# fig4-9.net
KiCad netlist of a schematic drawn in EAGLE
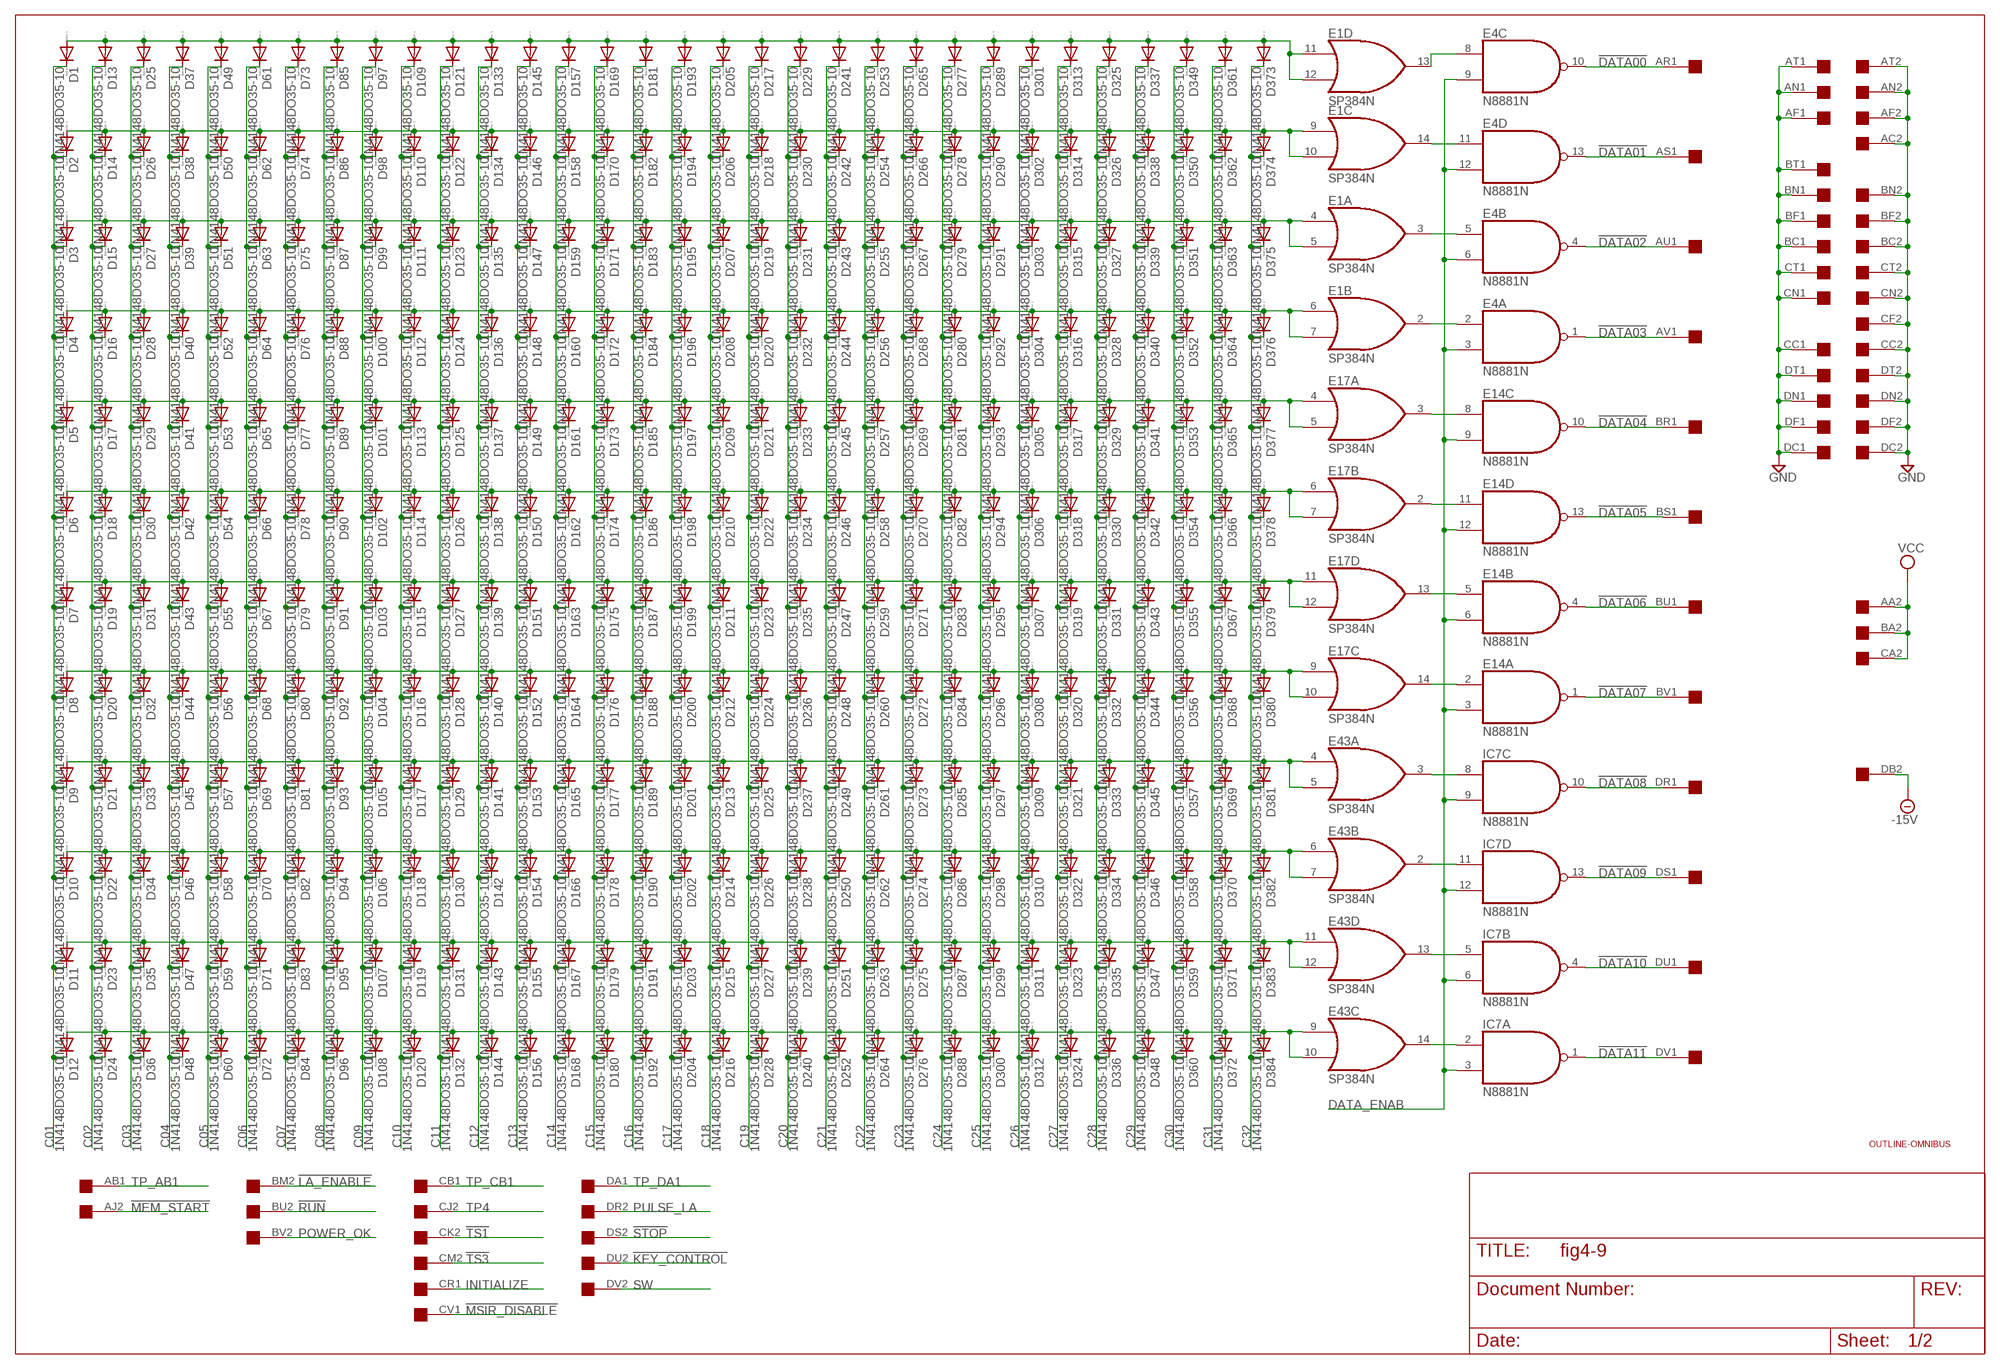
[diagram p0: schematic, sheet 1]
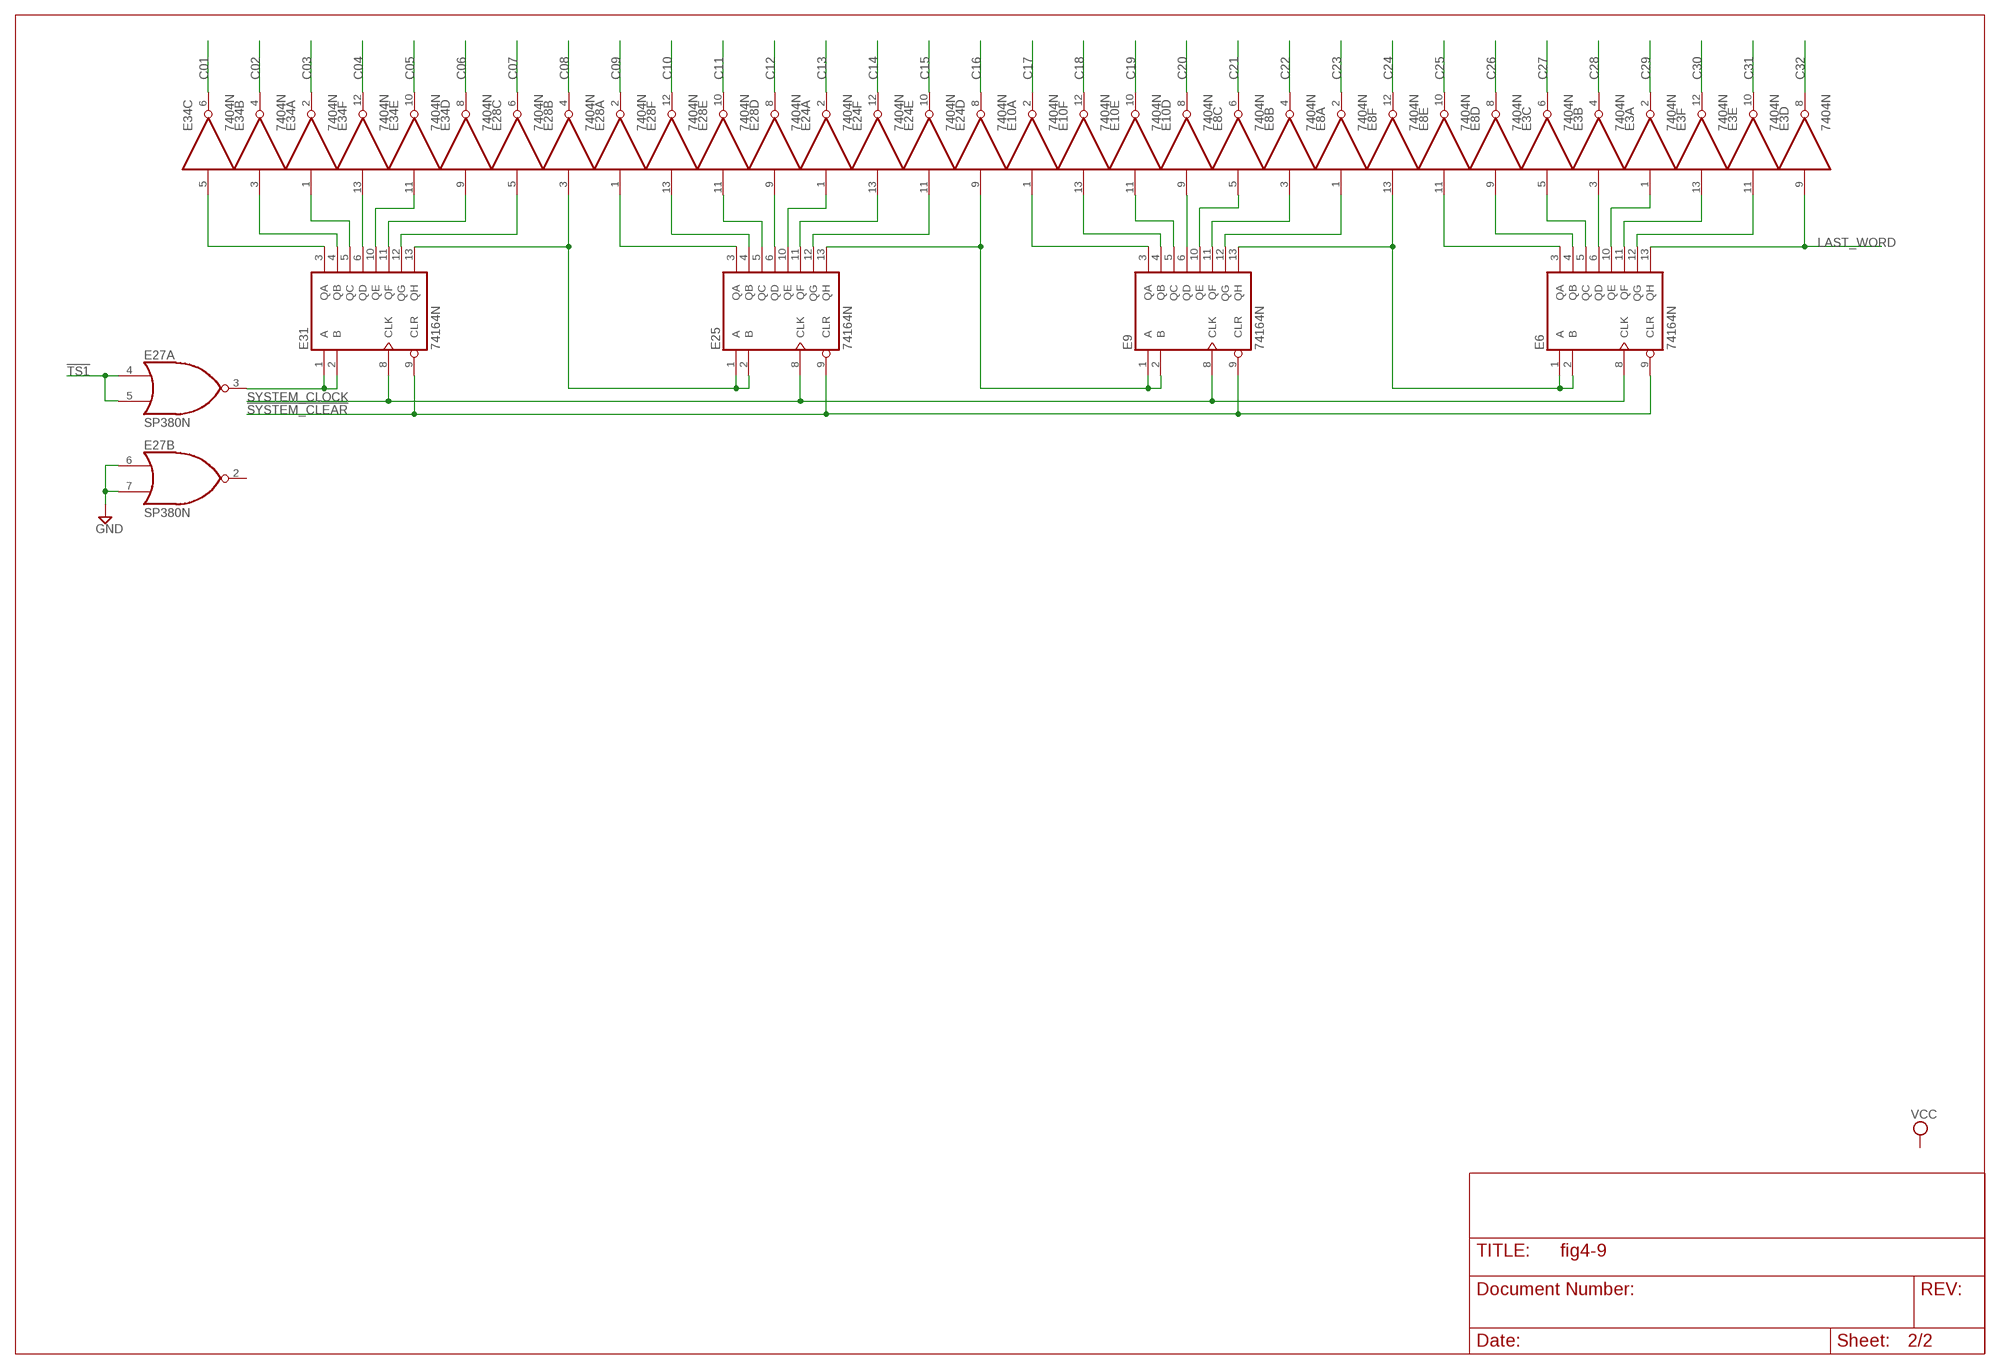
[diagram p1: schematic, sheet 2]

(export (version "E")
  (design (tool "Eeschema 10.0.6"))
  (components
    (comp (ref "D1")
      (value "1N4148DO35-10")
      (footprint "eagle-import:DO35-10")
      (libsource (lib "eagle-import") (part "1N4148DO35-10"))
    )
    (comp (ref "D2")
      (value "1N4148DO35-10")
      (footprint "eagle-import:DO35-10")
      (libsource (lib "eagle-import") (part "1N4148DO35-10"))
    )
    (comp (ref "D3")
      (value "1N4148DO35-10")
      (footprint "eagle-import:DO35-10")
      (libsource (lib "eagle-import") (part "1N4148DO35-10"))
    )
    (comp (ref "D4")
      (value "1N4148DO35-10")
      (footprint "eagle-import:DO35-10")
      (libsource (lib "eagle-import") (part "1N4148DO35-10"))
    )
    (comp (ref "D5")
      (value "1N4148DO35-10")
      (footprint "eagle-import:DO35-10")
      (libsource (lib "eagle-import") (part "1N4148DO35-10"))
    )
    (comp (ref "D6")
      (value "1N4148DO35-10")
      (footprint "eagle-import:DO35-10")
      (libsource (lib "eagle-import") (part "1N4148DO35-10"))
    )
    (comp (ref "D7")
      (value "1N4148DO35-10")
      (footprint "eagle-import:DO35-10")
      (libsource (lib "eagle-import") (part "1N4148DO35-10"))
    )
    (comp (ref "D8")
      (value "1N4148DO35-10")
      (footprint "eagle-import:DO35-10")
      (libsource (lib "eagle-import") (part "1N4148DO35-10"))
    )
    (comp (ref "D9")
      (value "1N4148DO35-10")
      (footprint "eagle-import:DO35-10")
      (libsource (lib "eagle-import") (part "1N4148DO35-10"))
    )
    (comp (ref "D10")
      (value "1N4148DO35-10")
      (footprint "eagle-import:DO35-10")
      (libsource (lib "eagle-import") (part "1N4148DO35-10"))
    )
    (comp (ref "D11")
      (value "1N4148DO35-10")
      (footprint "eagle-import:DO35-10")
      (libsource (lib "eagle-import") (part "1N4148DO35-10"))
    )
    (comp (ref "D12")
      (value "1N4148DO35-10")
      (footprint "eagle-import:DO35-10")
      (libsource (lib "eagle-import") (part "1N4148DO35-10"))
    )
    (comp (ref "D13")
      (value "1N4148DO35-10")
      (footprint "eagle-import:DO35-10")
      (libsource (lib "eagle-import") (part "1N4148DO35-10"))
    )
    (comp (ref "D14")
      (value "1N4148DO35-10")
      (footprint "eagle-import:DO35-10")
      (libsource (lib "eagle-import") (part "1N4148DO35-10"))
    )
    (comp (ref "D15")
      (value "1N4148DO35-10")
      (footprint "eagle-import:DO35-10")
      (libsource (lib "eagle-import") (part "1N4148DO35-10"))
    )
    (comp (ref "D16")
      (value "1N4148DO35-10")
      (footprint "eagle-import:DO35-10")
      (libsource (lib "eagle-import") (part "1N4148DO35-10"))
    )
    (comp (ref "D17")
      (value "1N4148DO35-10")
      (footprint "eagle-import:DO35-10")
      (libsource (lib "eagle-import") (part "1N4148DO35-10"))
    )
    (comp (ref "D18")
      (value "1N4148DO35-10")
      (footprint "eagle-import:DO35-10")
      (libsource (lib "eagle-import") (part "1N4148DO35-10"))
    )
    (comp (ref "D19")
      (value "1N4148DO35-10")
      (footprint "eagle-import:DO35-10")
      (libsource (lib "eagle-import") (part "1N4148DO35-10"))
    )
    (comp (ref "D20")
      (value "1N4148DO35-10")
      (footprint "eagle-import:DO35-10")
      (libsource (lib "eagle-import") (part "1N4148DO35-10"))
    )
    (comp (ref "D21")
      (value "1N4148DO35-10")
      (footprint "eagle-import:DO35-10")
      (libsource (lib "eagle-import") (part "1N4148DO35-10"))
    )
    (comp (ref "D22")
      (value "1N4148DO35-10")
      (footprint "eagle-import:DO35-10")
      (libsource (lib "eagle-import") (part "1N4148DO35-10"))
    )
    (comp (ref "D23")
      (value "1N4148DO35-10")
      (footprint "eagle-import:DO35-10")
      (libsource (lib "eagle-import") (part "1N4148DO35-10"))
    )
    (comp (ref "D24")
      (value "1N4148DO35-10")
      (footprint "eagle-import:DO35-10")
      (libsource (lib "eagle-import") (part "1N4148DO35-10"))
    )
    (comp (ref "D25")
      (value "1N4148DO35-10")
      (footprint "eagle-import:DO35-10")
      (libsource (lib "eagle-import") (part "1N4148DO35-10"))
    )
    (comp (ref "D26")
      (value "1N4148DO35-10")
      (footprint "eagle-import:DO35-10")
      (libsource (lib "eagle-import") (part "1N4148DO35-10"))
    )
    (comp (ref "D27")
      (value "1N4148DO35-10")
      (footprint "eagle-import:DO35-10")
      (libsource (lib "eagle-import") (part "1N4148DO35-10"))
    )
    (comp (ref "D28")
      (value "1N4148DO35-10")
      (footprint "eagle-import:DO35-10")
      (libsource (lib "eagle-import") (part "1N4148DO35-10"))
    )
    (comp (ref "D29")
      (value "1N4148DO35-10")
      (footprint "eagle-import:DO35-10")
      (libsource (lib "eagle-import") (part "1N4148DO35-10"))
    )
    (comp (ref "D30")
      (value "1N4148DO35-10")
      (footprint "eagle-import:DO35-10")
      (libsource (lib "eagle-import") (part "1N4148DO35-10"))
    )
    (comp (ref "D31")
      (value "1N4148DO35-10")
      (footprint "eagle-import:DO35-10")
      (libsource (lib "eagle-import") (part "1N4148DO35-10"))
    )
    (comp (ref "D32")
      (value "1N4148DO35-10")
      (footprint "eagle-import:DO35-10")
      (libsource (lib "eagle-import") (part "1N4148DO35-10"))
    )
    (comp (ref "D33")
      (value "1N4148DO35-10")
      (footprint "eagle-import:DO35-10")
      (libsource (lib "eagle-import") (part "1N4148DO35-10"))
    )
    (comp (ref "D34")
      (value "1N4148DO35-10")
      (footprint "eagle-import:DO35-10")
      (libsource (lib "eagle-import") (part "1N4148DO35-10"))
    )
    (comp (ref "D35")
      (value "1N4148DO35-10")
      (footprint "eagle-import:DO35-10")
      (libsource (lib "eagle-import") (part "1N4148DO35-10"))
    )
    (comp (ref "D36")
      (value "1N4148DO35-10")
      (footprint "eagle-import:DO35-10")
      (libsource (lib "eagle-import") (part "1N4148DO35-10"))
    )
    (comp (ref "D37")
      (value "1N4148DO35-10")
      (footprint "eagle-import:DO35-10")
      (libsource (lib "eagle-import") (part "1N4148DO35-10"))
    )
    (comp (ref "D38")
      (value "1N4148DO35-10")
      (footprint "eagle-import:DO35-10")
      (libsource (lib "eagle-import") (part "1N4148DO35-10"))
    )
    (comp (ref "D39")
      (value "1N4148DO35-10")
      (footprint "eagle-import:DO35-10")
      (libsource (lib "eagle-import") (part "1N4148DO35-10"))
    )
    (comp (ref "D40")
      (value "1N4148DO35-10")
      (footprint "eagle-import:DO35-10")
      (libsource (lib "eagle-import") (part "1N4148DO35-10"))
    )
    (comp (ref "D41")
      (value "1N4148DO35-10")
      (footprint "eagle-import:DO35-10")
      (libsource (lib "eagle-import") (part "1N4148DO35-10"))
    )
    (comp (ref "D42")
      (value "1N4148DO35-10")
      (footprint "eagle-import:DO35-10")
      (libsource (lib "eagle-import") (part "1N4148DO35-10"))
    )
    (comp (ref "D43")
      (value "1N4148DO35-10")
      (footprint "eagle-import:DO35-10")
      (libsource (lib "eagle-import") (part "1N4148DO35-10"))
    )
    (comp (ref "D44")
      (value "1N4148DO35-10")
      (footprint "eagle-import:DO35-10")
      (libsource (lib "eagle-import") (part "1N4148DO35-10"))
    )
    (comp (ref "D45")
      (value "1N4148DO35-10")
      (footprint "eagle-import:DO35-10")
      (libsource (lib "eagle-import") (part "1N4148DO35-10"))
    )
    (comp (ref "D46")
      (value "1N4148DO35-10")
      (footprint "eagle-import:DO35-10")
      (libsource (lib "eagle-import") (part "1N4148DO35-10"))
    )
    (comp (ref "D47")
      (value "1N4148DO35-10")
      (footprint "eagle-import:DO35-10")
      (libsource (lib "eagle-import") (part "1N4148DO35-10"))
    )
    (comp (ref "D48")
      (value "1N4148DO35-10")
      (footprint "eagle-import:DO35-10")
      (libsource (lib "eagle-import") (part "1N4148DO35-10"))
    )
    (comp (ref "D49")
      (value "1N4148DO35-10")
      (footprint "eagle-import:DO35-10")
      (libsource (lib "eagle-import") (part "1N4148DO35-10"))
    )
    (comp (ref "D50")
      (value "1N4148DO35-10")
      (footprint "eagle-import:DO35-10")
      (libsource (lib "eagle-import") (part "1N4148DO35-10"))
    )
    (comp (ref "D51")
      (value "1N4148DO35-10")
      (footprint "eagle-import:DO35-10")
      (libsource (lib "eagle-import") (part "1N4148DO35-10"))
    )
    (comp (ref "D52")
      (value "1N4148DO35-10")
      (footprint "eagle-import:DO35-10")
      (libsource (lib "eagle-import") (part "1N4148DO35-10"))
    )
    (comp (ref "D53")
      (value "1N4148DO35-10")
      (footprint "eagle-import:DO35-10")
      (libsource (lib "eagle-import") (part "1N4148DO35-10"))
    )
    (comp (ref "D54")
      (value "1N4148DO35-10")
      (footprint "eagle-import:DO35-10")
      (libsource (lib "eagle-import") (part "1N4148DO35-10"))
    )
    (comp (ref "D55")
      (value "1N4148DO35-10")
      (footprint "eagle-import:DO35-10")
      (libsource (lib "eagle-import") (part "1N4148DO35-10"))
    )
    (comp (ref "D56")
      (value "1N4148DO35-10")
      (footprint "eagle-import:DO35-10")
      (libsource (lib "eagle-import") (part "1N4148DO35-10"))
    )
    (comp (ref "D57")
      (value "1N4148DO35-10")
      (footprint "eagle-import:DO35-10")
      (libsource (lib "eagle-import") (part "1N4148DO35-10"))
    )
    (comp (ref "D58")
      (value "1N4148DO35-10")
      (footprint "eagle-import:DO35-10")
      (libsource (lib "eagle-import") (part "1N4148DO35-10"))
    )
    (comp (ref "D59")
      (value "1N4148DO35-10")
      (footprint "eagle-import:DO35-10")
      (libsource (lib "eagle-import") (part "1N4148DO35-10"))
    )
    (comp (ref "D60")
      (value "1N4148DO35-10")
      (footprint "eagle-import:DO35-10")
      (libsource (lib "eagle-import") (part "1N4148DO35-10"))
    )
    (comp (ref "D61")
      (value "1N4148DO35-10")
      (footprint "eagle-import:DO35-10")
      (libsource (lib "eagle-import") (part "1N4148DO35-10"))
    )
    (comp (ref "D62")
      (value "1N4148DO35-10")
      (footprint "eagle-import:DO35-10")
      (libsource (lib "eagle-import") (part "1N4148DO35-10"))
    )
    (comp (ref "D63")
      (value "1N4148DO35-10")
      (footprint "eagle-import:DO35-10")
      (libsource (lib "eagle-import") (part "1N4148DO35-10"))
    )
    (comp (ref "D64")
      (value "1N4148DO35-10")
      (footprint "eagle-import:DO35-10")
      (libsource (lib "eagle-import") (part "1N4148DO35-10"))
    )
    (comp (ref "D65")
      (value "1N4148DO35-10")
      (footprint "eagle-import:DO35-10")
      (libsource (lib "eagle-import") (part "1N4148DO35-10"))
    )
    (comp (ref "D66")
      (value "1N4148DO35-10")
      (footprint "eagle-import:DO35-10")
      (libsource (lib "eagle-import") (part "1N4148DO35-10"))
    )
    (comp (ref "D67")
      (value "1N4148DO35-10")
      (footprint "eagle-import:DO35-10")
      (libsource (lib "eagle-import") (part "1N4148DO35-10"))
    )
    (comp (ref "D68")
      (value "1N4148DO35-10")
      (footprint "eagle-import:DO35-10")
      (libsource (lib "eagle-import") (part "1N4148DO35-10"))
    )
    (comp (ref "D69")
      (value "1N4148DO35-10")
      (footprint "eagle-import:DO35-10")
      (libsource (lib "eagle-import") (part "1N4148DO35-10"))
    )
    (comp (ref "D70")
      (value "1N4148DO35-10")
      (footprint "eagle-import:DO35-10")
      (libsource (lib "eagle-import") (part "1N4148DO35-10"))
    )
    (comp (ref "D71")
      (value "1N4148DO35-10")
      (footprint "eagle-import:DO35-10")
      (libsource (lib "eagle-import") (part "1N4148DO35-10"))
    )
    (comp (ref "D72")
      (value "1N4148DO35-10")
      (footprint "eagle-import:DO35-10")
      (libsource (lib "eagle-import") (part "1N4148DO35-10"))
    )
    (comp (ref "D73")
      (value "1N4148DO35-10")
      (footprint "eagle-import:DO35-10")
      (libsource (lib "eagle-import") (part "1N4148DO35-10"))
    )
    (comp (ref "D74")
      (value "1N4148DO35-10")
      (footprint "eagle-import:DO35-10")
      (libsource (lib "eagle-import") (part "1N4148DO35-10"))
    )
    (comp (ref "D75")
      (value "1N4148DO35-10")
      (footprint "eagle-import:DO35-10")
      (libsource (lib "eagle-import") (part "1N4148DO35-10"))
    )
    (comp (ref "D76")
      (value "1N4148DO35-10")
      (footprint "eagle-import:DO35-10")
      (libsource (lib "eagle-import") (part "1N4148DO35-10"))
    )
    (comp (ref "D77")
      (value "1N4148DO35-10")
      (footprint "eagle-import:DO35-10")
      (libsource (lib "eagle-import") (part "1N4148DO35-10"))
    )
    (comp (ref "D78")
      (value "1N4148DO35-10")
      (footprint "eagle-import:DO35-10")
      (libsource (lib "eagle-import") (part "1N4148DO35-10"))
    )
    (comp (ref "D79")
      (value "1N4148DO35-10")
      (footprint "eagle-import:DO35-10")
      (libsource (lib "eagle-import") (part "1N4148DO35-10"))
    )
    (comp (ref "D80")
      (value "1N4148DO35-10")
      (footprint "eagle-import:DO35-10")
      (libsource (lib "eagle-import") (part "1N4148DO35-10"))
    )
    (comp (ref "D81")
      (value "1N4148DO35-10")
      (footprint "eagle-import:DO35-10")
      (libsource (lib "eagle-import") (part "1N4148DO35-10"))
    )
    (comp (ref "D82")
      (value "1N4148DO35-10")
      (footprint "eagle-import:DO35-10")
      (libsource (lib "eagle-import") (part "1N4148DO35-10"))
    )
    (comp (ref "D83")
      (value "1N4148DO35-10")
      (footprint "eagle-import:DO35-10")
      (libsource (lib "eagle-import") (part "1N4148DO35-10"))
    )
    (comp (ref "D84")
      (value "1N4148DO35-10")
      (footprint "eagle-import:DO35-10")
      (libsource (lib "eagle-import") (part "1N4148DO35-10"))
    )
    (comp (ref "D85")
      (value "1N4148DO35-10")
      (footprint "eagle-import:DO35-10")
      (libsource (lib "eagle-import") (part "1N4148DO35-10"))
    )
    (comp (ref "D86")
      (value "1N4148DO35-10")
      (footprint "eagle-import:DO35-10")
      (libsource (lib "eagle-import") (part "1N4148DO35-10"))
    )
    (comp (ref "D87")
      (value "1N4148DO35-10")
      (footprint "eagle-import:DO35-10")
      (libsource (lib "eagle-import") (part "1N4148DO35-10"))
    )
    (comp (ref "D88")
      (value "1N4148DO35-10")
      (footprint "eagle-import:DO35-10")
      (libsource (lib "eagle-import") (part "1N4148DO35-10"))
    )
    (comp (ref "D89")
      (value "1N4148DO35-10")
      (footprint "eagle-import:DO35-10")
      (libsource (lib "eagle-import") (part "1N4148DO35-10"))
    )
    (comp (ref "D90")
      (value "1N4148DO35-10")
      (footprint "eagle-import:DO35-10")
      (libsource (lib "eagle-import") (part "1N4148DO35-10"))
    )
    (comp (ref "D91")
      (value "1N4148DO35-10")
      (footprint "eagle-import:DO35-10")
      (libsource (lib "eagle-import") (part "1N4148DO35-10"))
    )
    (comp (ref "D92")
      (value "1N4148DO35-10")
      (footprint "eagle-import:DO35-10")
      (libsource (lib "eagle-import") (part "1N4148DO35-10"))
    )
    (comp (ref "D93")
      (value "1N4148DO35-10")
      (footprint "eagle-import:DO35-10")
      (libsource (lib "eagle-import") (part "1N4148DO35-10"))
    )
    (comp (ref "D94")
      (value "1N4148DO35-10")
      (footprint "eagle-import:DO35-10")
      (libsource (lib "eagle-import") (part "1N4148DO35-10"))
    )
    (comp (ref "D95")
      (value "1N4148DO35-10")
      (footprint "eagle-import:DO35-10")
      (libsource (lib "eagle-import") (part "1N4148DO35-10"))
    )
    (comp (ref "D96")
      (value "1N4148DO35-10")
      (footprint "eagle-import:DO35-10")
      (libsource (lib "eagle-import") (part "1N4148DO35-10"))
    )
    (comp (ref "D97")
      (value "1N4148DO35-10")
      (footprint "eagle-import:DO35-10")
      (libsource (lib "eagle-import") (part "1N4148DO35-10"))
    )
    (comp (ref "D98")
      (value "1N4148DO35-10")
      (footprint "eagle-import:DO35-10")
      (libsource (lib "eagle-import") (part "1N4148DO35-10"))
    )
    (comp (ref "D99")
      (value "1N4148DO35-10")
      (footprint "eagle-import:DO35-10")
      (libsource (lib "eagle-import") (part "1N4148DO35-10"))
    )
    (comp (ref "D100")
      (value "1N4148DO35-10")
      (footprint "eagle-import:DO35-10")
      (libsource (lib "eagle-import") (part "1N4148DO35-10"))
    )
    (comp (ref "D101")
      (value "1N4148DO35-10")
      (footprint "eagle-import:DO35-10")
      (libsource (lib "eagle-import") (part "1N4148DO35-10"))
    )
    (comp (ref "D102")
      (value "1N4148DO35-10")
      (footprint "eagle-import:DO35-10")
      (libsource (lib "eagle-import") (part "1N4148DO35-10"))
    )
    (comp (ref "D103")
      (value "1N4148DO35-10")
      (footprint "eagle-import:DO35-10")
      (libsource (lib "eagle-import") (part "1N4148DO35-10"))
    )
    (comp (ref "D104")
      (value "1N4148DO35-10")
      (footprint "eagle-import:DO35-10")
      (libsource (lib "eagle-import") (part "1N4148DO35-10"))
    )
    (comp (ref "D105")
      (value "1N4148DO35-10")
      (footprint "eagle-import:DO35-10")
      (libsource (lib "eagle-import") (part "1N4148DO35-10"))
    )
    (comp (ref "D106")
      (value "1N4148DO35-10")
      (footprint "eagle-import:DO35-10")
      (libsource (lib "eagle-import") (part "1N4148DO35-10"))
    )
    (comp (ref "D107")
      (value "1N4148DO35-10")
      (footprint "eagle-import:DO35-10")
      (libsource (lib "eagle-import") (part "1N4148DO35-10"))
    )
    (comp (ref "D108")
      (value "1N4148DO35-10")
      (footprint "eagle-import:DO35-10")
      (libsource (lib "eagle-import") (part "1N4148DO35-10"))
    )
    (comp (ref "D109")
      (value "1N4148DO35-10")
      (footprint "eagle-import:DO35-10")
      (libsource (lib "eagle-import") (part "1N4148DO35-10"))
    )
    (comp (ref "D110")
      (value "1N4148DO35-10")
      (footprint "eagle-import:DO35-10")
      (libsource (lib "eagle-import") (part "1N4148DO35-10"))
    )
    (comp (ref "D111")
      (value "1N4148DO35-10")
      (footprint "eagle-import:DO35-10")
      (libsource (lib "eagle-import") (part "1N4148DO35-10"))
    )
    (comp (ref "D112")
      (value "1N4148DO35-10")
      (footprint "eagle-import:DO35-10")
      (libsource (lib "eagle-import") (part "1N4148DO35-10"))
    )
    (comp (ref "D113")
      (value "1N4148DO35-10")
      (footprint "eagle-import:DO35-10")
      (libsource (lib "eagle-import") (part "1N4148DO35-10"))
    )
    (comp (ref "D114")
      (value "1N4148DO35-10")
      (footprint "eagle-import:DO35-10")
      (libsource (lib "eagle-import") (part "1N4148DO35-10"))
    )
    (comp (ref "D115")
      (value "1N4148DO35-10")
      (footprint "eagle-import:DO35-10")
      (libsource (lib "eagle-import") (part "1N4148DO35-10"))
    )
    (comp (ref "D116")
      (value "1N4148DO35-10")
      (footprint "eagle-import:DO35-10")
      (libsource (lib "eagle-import") (part "1N4148DO35-10"))
    )
    (comp (ref "D117")
      (value "1N4148DO35-10")
      (footprint "eagle-import:DO35-10")
      (libsource (lib "eagle-import") (part "1N4148DO35-10"))
    )
    (comp (ref "D118")
      (value "1N4148DO35-10")
      (footprint "eagle-import:DO35-10")
      (libsource (lib "eagle-import") (part "1N4148DO35-10"))
    )
    (comp (ref "D119")
      (value "1N4148DO35-10")
      (footprint "eagle-import:DO35-10")
      (libsource (lib "eagle-import") (part "1N4148DO35-10"))
    )
    (comp (ref "D120")
      (value "1N4148DO35-10")
      (footprint "eagle-import:DO35-10")
      (libsource (lib "eagle-import") (part "1N4148DO35-10"))
    )
    (comp (ref "D121")
      (value "1N4148DO35-10")
      (footprint "eagle-import:DO35-10")
      (libsource (lib "eagle-import") (part "1N4148DO35-10"))
    )
    (comp (ref "D122")
      (value "1N4148DO35-10")
      (footprint "eagle-import:DO35-10")
      (libsource (lib "eagle-import") (part "1N4148DO35-10"))
    )
    (comp (ref "D123")
      (value "1N4148DO35-10")
      (footprint "eagle-import:DO35-10")
      (libsource (lib "eagle-import") (part "1N4148DO35-10"))
    )
    (comp (ref "D124")
      (value "1N4148DO35-10")
      (footprint "eagle-import:DO35-10")
      (libsource (lib "eagle-import") (part "1N4148DO35-10"))
    )
    (comp (ref "D125")
      (value "1N4148DO35-10")
      (footprint "eagle-import:DO35-10")
      (libsource (lib "eagle-import") (part "1N4148DO35-10"))
    )
    (comp (ref "D126")
      (value "1N4148DO35-10")
      (footprint "eagle-import:DO35-10")
      (libsource (lib "eagle-import") (part "1N4148DO35-10"))
    )
    (comp (ref "D127")
      (value "1N4148DO35-10")
      (footprint "eagle-import:DO35-10")
      (libsource (lib "eagle-import") (part "1N4148DO35-10"))
    )
    (comp (ref "D128")
      (value "1N4148DO35-10")
      (footprint "eagle-import:DO35-10")
      (libsource (lib "eagle-import") (part "1N4148DO35-10"))
    )
    (comp (ref "D129")
      (value "1N4148DO35-10")
      (footprint "eagle-import:DO35-10")
      (libsource (lib "eagle-import") (part "1N4148DO35-10"))
    )
    (comp (ref "D130")
      (value "1N4148DO35-10")
      (footprint "eagle-import:DO35-10")
      (libsource (lib "eagle-import") (part "1N4148DO35-10"))
    )
    (comp (ref "D131")
      (value "1N4148DO35-10")
      (footprint "eagle-import:DO35-10")
      (libsource (lib "eagle-import") (part "1N4148DO35-10"))
    )
    (comp (ref "D132")
      (value "1N4148DO35-10")
      (footprint "eagle-import:DO35-10")
      (libsource (lib "eagle-import") (part "1N4148DO35-10"))
    )
    (comp (ref "D133")
      (value "1N4148DO35-10")
      (footprint "eagle-import:DO35-10")
      (libsource (lib "eagle-import") (part "1N4148DO35-10"))
    )
    (comp (ref "D134")
      (value "1N4148DO35-10")
      (footprint "eagle-import:DO35-10")
      (libsource (lib "eagle-import") (part "1N4148DO35-10"))
    )
    (comp (ref "D135")
      (value "1N4148DO35-10")
      (footprint "eagle-import:DO35-10")
      (libsource (lib "eagle-import") (part "1N4148DO35-10"))
    )
    (comp (ref "D136")
      (value "1N4148DO35-10")
      (footprint "eagle-import:DO35-10")
      (libsource (lib "eagle-import") (part "1N4148DO35-10"))
    )
    (comp (ref "D137")
      (value "1N4148DO35-10")
      (footprint "eagle-import:DO35-10")
      (libsource (lib "eagle-import") (part "1N4148DO35-10"))
    )
    (comp (ref "D138")
      (value "1N4148DO35-10")
      (footprint "eagle-import:DO35-10")
      (libsource (lib "eagle-import") (part "1N4148DO35-10"))
    )
    (comp (ref "D139")
      (value "1N4148DO35-10")
      (footprint "eagle-import:DO35-10")
      (libsource (lib "eagle-import") (part "1N4148DO35-10"))
    )
    (comp (ref "D140")
      (value "1N4148DO35-10")
      (footprint "eagle-import:DO35-10")
      (libsource (lib "eagle-import") (part "1N4148DO35-10"))
    )
    (comp (ref "D141")
      (value "1N4148DO35-10")
      (footprint "eagle-import:DO35-10")
      (libsource (lib "eagle-import") (part "1N4148DO35-10"))
    )
    (comp (ref "D142")
      (value "1N4148DO35-10")
      (footprint "eagle-import:DO35-10")
      (libsource (lib "eagle-import") (part "1N4148DO35-10"))
    )
    (comp (ref "D143")
      (value "1N4148DO35-10")
      (footprint "eagle-import:DO35-10")
      (libsource (lib "eagle-import") (part "1N4148DO35-10"))
    )
    (comp (ref "D144")
      (value "1N4148DO35-10")
      (footprint "eagle-import:DO35-10")
      (libsource (lib "eagle-import") (part "1N4148DO35-10"))
    )
    (comp (ref "D145")
      (value "1N4148DO35-10")
      (footprint "eagle-import:DO35-10")
      (libsource (lib "eagle-import") (part "1N4148DO35-10"))
    )
    (comp (ref "D146")
      (value "1N4148DO35-10")
      (footprint "eagle-import:DO35-10")
      (libsource (lib "eagle-import") (part "1N4148DO35-10"))
    )
    (comp (ref "D147")
      (value "1N4148DO35-10")
      (footprint "eagle-import:DO35-10")
      (libsource (lib "eagle-import") (part "1N4148DO35-10"))
    )
    (comp (ref "D148")
      (value "1N4148DO35-10")
      (footprint "eagle-import:DO35-10")
      (libsource (lib "eagle-import") (part "1N4148DO35-10"))
    )
    (comp (ref "D149")
      (value "1N4148DO35-10")
      (footprint "eagle-import:DO35-10")
      (libsource (lib "eagle-import") (part "1N4148DO35-10"))
    )
    (comp (ref "D150")
      (value "1N4148DO35-10")
      (footprint "eagle-import:DO35-10")
      (libsource (lib "eagle-import") (part "1N4148DO35-10"))
    )
    (comp (ref "D151")
      (value "1N4148DO35-10")
      (footprint "eagle-import:DO35-10")
      (libsource (lib "eagle-import") (part "1N4148DO35-10"))
    )
    (comp (ref "D152")
      (value "1N4148DO35-10")
      (footprint "eagle-import:DO35-10")
      (libsource (lib "eagle-import") (part "1N4148DO35-10"))
    )
    (comp (ref "D153")
      (value "1N4148DO35-10")
      (footprint "eagle-import:DO35-10")
      (libsource (lib "eagle-import") (part "1N4148DO35-10"))
    )
    (comp (ref "D154")
      (value "1N4148DO35-10")
      (footprint "eagle-import:DO35-10")
      (libsource (lib "eagle-import") (part "1N4148DO35-10"))
    )
    (comp (ref "D155")
      (value "1N4148DO35-10")
      (footprint "eagle-import:DO35-10")
      (libsource (lib "eagle-import") (part "1N4148DO35-10"))
    )
    (comp (ref "D156")
      (value "1N4148DO35-10")
      (footprint "eagle-import:DO35-10")
      (libsource (lib "eagle-import") (part "1N4148DO35-10"))
    )
    (comp (ref "D157")
      (value "1N4148DO35-10")
      (footprint "eagle-import:DO35-10")
      (libsource (lib "eagle-import") (part "1N4148DO35-10"))
    )
    (comp (ref "D158")
      (value "1N4148DO35-10")
      (footprint "eagle-import:DO35-10")
      (libsource (lib "eagle-import") (part "1N4148DO35-10"))
    )
    (comp (ref "D159")
      (value "1N4148DO35-10")
      (footprint "eagle-import:DO35-10")
      (libsource (lib "eagle-import") (part "1N4148DO35-10"))
    )
    (comp (ref "D160")
      (value "1N4148DO35-10")
      (footprint "eagle-import:DO35-10")
      (libsource (lib "eagle-import") (part "1N4148DO35-10"))
    )
    (comp (ref "D161")
      (value "1N4148DO35-10")
      (footprint "eagle-import:DO35-10")
      (libsource (lib "eagle-import") (part "1N4148DO35-10"))
    )
    (comp (ref "D162")
      (value "1N4148DO35-10")
      (footprint "eagle-import:DO35-10")
      (libsource (lib "eagle-import") (part "1N4148DO35-10"))
    )
    (comp (ref "D163")
      (value "1N4148DO35-10")
      (footprint "eagle-import:DO35-10")
      (libsource (lib "eagle-import") (part "1N4148DO35-10"))
    )
    (comp (ref "D164")
      (value "1N4148DO35-10")
      (footprint "eagle-import:DO35-10")
      (libsource (lib "eagle-import") (part "1N4148DO35-10"))
    )
    (comp (ref "D165")
      (value "1N4148DO35-10")
      (footprint "eagle-import:DO35-10")
      (libsource (lib "eagle-import") (part "1N4148DO35-10"))
    )
    (comp (ref "D166")
      (value "1N4148DO35-10")
      (footprint "eagle-import:DO35-10")
      (libsource (lib "eagle-import") (part "1N4148DO35-10"))
    )
    (comp (ref "D167")
      (value "1N4148DO35-10")
      (footprint "eagle-import:DO35-10")
      (libsource (lib "eagle-import") (part "1N4148DO35-10"))
    )
    (comp (ref "D168")
      (value "1N4148DO35-10")
      (footprint "eagle-import:DO35-10")
      (libsource (lib "eagle-import") (part "1N4148DO35-10"))
    )
    (comp (ref "D169")
      (value "1N4148DO35-10")
      (footprint "eagle-import:DO35-10")
      (libsource (lib "eagle-import") (part "1N4148DO35-10"))
    )
    (comp (ref "D170")
      (value "1N4148DO35-10")
      (footprint "eagle-import:DO35-10")
      (libsource (lib "eagle-import") (part "1N4148DO35-10"))
    )
    (comp (ref "D171")
      (value "1N4148DO35-10")
      (footprint "eagle-import:DO35-10")
      (libsource (lib "eagle-import") (part "1N4148DO35-10"))
    )
    (comp (ref "D172")
      (value "1N4148DO35-10")
      (footprint "eagle-import:DO35-10")
      (libsource (lib "eagle-import") (part "1N4148DO35-10"))
    )
    (comp (ref "D173")
      (value "1N4148DO35-10")
      (footprint "eagle-import:DO35-10")
      (libsource (lib "eagle-import") (part "1N4148DO35-10"))
    )
    (comp (ref "D174")
      (value "1N4148DO35-10")
      (footprint "eagle-import:DO35-10")
      (libsource (lib "eagle-import") (part "1N4148DO35-10"))
    )
    (comp (ref "D175")
      (value "1N4148DO35-10")
      (footprint "eagle-import:DO35-10")
      (libsource (lib "eagle-import") (part "1N4148DO35-10"))
    )
    (comp (ref "D176")
      (value "1N4148DO35-10")
      (footprint "eagle-import:DO35-10")
      (libsource (lib "eagle-import") (part "1N4148DO35-10"))
    )
    (comp (ref "D177")
      (value "1N4148DO35-10")
      (footprint "eagle-import:DO35-10")
      (libsource (lib "eagle-import") (part "1N4148DO35-10"))
    )
    (comp (ref "D178")
      (value "1N4148DO35-10")
      (footprint "eagle-import:DO35-10")
      (libsource (lib "eagle-import") (part "1N4148DO35-10"))
    )
    (comp (ref "D179")
      (value "1N4148DO35-10")
      (footprint "eagle-import:DO35-10")
      (libsource (lib "eagle-import") (part "1N4148DO35-10"))
    )
    (comp (ref "D180")
      (value "1N4148DO35-10")
      (footprint "eagle-import:DO35-10")
      (libsource (lib "eagle-import") (part "1N4148DO35-10"))
    )
    (comp (ref "D181")
      (value "1N4148DO35-10")
      (footprint "eagle-import:DO35-10")
      (libsource (lib "eagle-import") (part "1N4148DO35-10"))
    )
    (comp (ref "D182")
      (value "1N4148DO35-10")
      (footprint "eagle-import:DO35-10")
      (libsource (lib "eagle-import") (part "1N4148DO35-10"))
    )
    (comp (ref "D183")
      (value "1N4148DO35-10")
      (footprint "eagle-import:DO35-10")
      (libsource (lib "eagle-import") (part "1N4148DO35-10"))
    )
    (comp (ref "D184")
      (value "1N4148DO35-10")
      (footprint "eagle-import:DO35-10")
      (libsource (lib "eagle-import") (part "1N4148DO35-10"))
    )
    (comp (ref "D185")
      (value "1N4148DO35-10")
      (footprint "eagle-import:DO35-10")
      (libsource (lib "eagle-import") (part "1N4148DO35-10"))
    )
    (comp (ref "D186")
      (value "1N4148DO35-10")
      (footprint "eagle-import:DO35-10")
      (libsource (lib "eagle-import") (part "1N4148DO35-10"))
    )
    (comp (ref "D187")
      (value "1N4148DO35-10")
      (footprint "eagle-import:DO35-10")
      (libsource (lib "eagle-import") (part "1N4148DO35-10"))
    )
    (comp (ref "D188")
      (value "1N4148DO35-10")
      (footprint "eagle-import:DO35-10")
      (libsource (lib "eagle-import") (part "1N4148DO35-10"))
    )
    (comp (ref "D189")
      (value "1N4148DO35-10")
      (footprint "eagle-import:DO35-10")
      (libsource (lib "eagle-import") (part "1N4148DO35-10"))
    )
    (comp (ref "D190")
      (value "1N4148DO35-10")
      (footprint "eagle-import:DO35-10")
      (libsource (lib "eagle-import") (part "1N4148DO35-10"))
    )
    (comp (ref "D191")
      (value "1N4148DO35-10")
      (footprint "eagle-import:DO35-10")
      (libsource (lib "eagle-import") (part "1N4148DO35-10"))
    )
    (comp (ref "D192")
      (value "1N4148DO35-10")
      (footprint "eagle-import:DO35-10")
      (libsource (lib "eagle-import") (part "1N4148DO35-10"))
    )
    (comp (ref "D193")
      (value "1N4148DO35-10")
      (footprint "eagle-import:DO35-10")
      (libsource (lib "eagle-import") (part "1N4148DO35-10"))
    )
    (comp (ref "D194")
      (value "1N4148DO35-10")
      (footprint "eagle-import:DO35-10")
      (libsource (lib "eagle-import") (part "1N4148DO35-10"))
    )
    (comp (ref "D195")
      (value "1N4148DO35-10")
      (footprint "eagle-import:DO35-10")
      (libsource (lib "eagle-import") (part "1N4148DO35-10"))
    )
    (comp (ref "D196")
      (value "1N4148DO35-10")
      (footprint "eagle-import:DO35-10")
      (libsource (lib "eagle-import") (part "1N4148DO35-10"))
    )
    (comp (ref "D197")
      (value "1N4148DO35-10")
      (footprint "eagle-import:DO35-10")
      (libsource (lib "eagle-import") (part "1N4148DO35-10"))
    )
    (comp (ref "D198")
      (value "1N4148DO35-10")
      (footprint "eagle-import:DO35-10")
      (libsource (lib "eagle-import") (part "1N4148DO35-10"))
    )
    (comp (ref "D199")
      (value "1N4148DO35-10")
      (footprint "eagle-import:DO35-10")
      (libsource (lib "eagle-import") (part "1N4148DO35-10"))
    )
    (comp (ref "D200")
      (value "1N4148DO35-10")
      (footprint "eagle-import:DO35-10")
      (libsource (lib "eagle-import") (part "1N4148DO35-10"))
    )
    (comp (ref "D201")
      (value "1N4148DO35-10")
      (footprint "eagle-import:DO35-10")
      (libsource (lib "eagle-import") (part "1N4148DO35-10"))
    )
    (comp (ref "D202")
      (value "1N4148DO35-10")
      (footprint "eagle-import:DO35-10")
      (libsource (lib "eagle-import") (part "1N4148DO35-10"))
    )
    (comp (ref "D203")
      (value "1N4148DO35-10")
      (footprint "eagle-import:DO35-10")
      (libsource (lib "eagle-import") (part "1N4148DO35-10"))
    )
    (comp (ref "D204")
      (value "1N4148DO35-10")
      (footprint "eagle-import:DO35-10")
      (libsource (lib "eagle-import") (part "1N4148DO35-10"))
    )
    (comp (ref "D205")
      (value "1N4148DO35-10")
      (footprint "eagle-import:DO35-10")
      (libsource (lib "eagle-import") (part "1N4148DO35-10"))
    )
    (comp (ref "D206")
      (value "1N4148DO35-10")
      (footprint "eagle-import:DO35-10")
      (libsource (lib "eagle-import") (part "1N4148DO35-10"))
    )
    (comp (ref "D207")
      (value "1N4148DO35-10")
      (footprint "eagle-import:DO35-10")
      (libsource (lib "eagle-import") (part "1N4148DO35-10"))
    )
    (comp (ref "D208")
      (value "1N4148DO35-10")
      (footprint "eagle-import:DO35-10")
      (libsource (lib "eagle-import") (part "1N4148DO35-10"))
    )
    (comp (ref "D209")
      (value "1N4148DO35-10")
      (footprint "eagle-import:DO35-10")
      (libsource (lib "eagle-import") (part "1N4148DO35-10"))
    )
    (comp (ref "D210")
      (value "1N4148DO35-10")
      (footprint "eagle-import:DO35-10")
      (libsource (lib "eagle-import") (part "1N4148DO35-10"))
    )
    (comp (ref "D211")
      (value "1N4148DO35-10")
      (footprint "eagle-import:DO35-10")
      (libsource (lib "eagle-import") (part "1N4148DO35-10"))
    )
    (comp (ref "D212")
      (value "1N4148DO35-10")
      (footprint "eagle-import:DO35-10")
      (libsource (lib "eagle-import") (part "1N4148DO35-10"))
    )
    (comp (ref "D213")
      (value "1N4148DO35-10")
      (footprint "eagle-import:DO35-10")
      (libsource (lib "eagle-import") (part "1N4148DO35-10"))
    )
    (comp (ref "D214")
      (value "1N4148DO35-10")
      (footprint "eagle-import:DO35-10")
      (libsource (lib "eagle-import") (part "1N4148DO35-10"))
    )
    (comp (ref "D215")
      (value "1N4148DO35-10")
      (footprint "eagle-import:DO35-10")
      (libsource (lib "eagle-import") (part "1N4148DO35-10"))
    )
    (comp (ref "D216")
      (value "1N4148DO35-10")
      (footprint "eagle-import:DO35-10")
      (libsource (lib "eagle-import") (part "1N4148DO35-10"))
    )
    (comp (ref "D217")
      (value "1N4148DO35-10")
      (footprint "eagle-import:DO35-10")
      (libsource (lib "eagle-import") (part "1N4148DO35-10"))
    )
    (comp (ref "D218")
      (value "1N4148DO35-10")
      (footprint "eagle-import:DO35-10")
      (libsource (lib "eagle-import") (part "1N4148DO35-10"))
    )
    (comp (ref "D219")
      (value "1N4148DO35-10")
      (footprint "eagle-import:DO35-10")
      (libsource (lib "eagle-import") (part "1N4148DO35-10"))
    )
    (comp (ref "D220")
      (value "1N4148DO35-10")
      (footprint "eagle-import:DO35-10")
      (libsource (lib "eagle-import") (part "1N4148DO35-10"))
    )
    (comp (ref "D221")
      (value "1N4148DO35-10")
      (footprint "eagle-import:DO35-10")
      (libsource (lib "eagle-import") (part "1N4148DO35-10"))
    )
    (comp (ref "D222")
      (value "1N4148DO35-10")
      (footprint "eagle-import:DO35-10")
      (libsource (lib "eagle-import") (part "1N4148DO35-10"))
    )
    (comp (ref "D223")
      (value "1N4148DO35-10")
      (footprint "eagle-import:DO35-10")
      (libsource (lib "eagle-import") (part "1N4148DO35-10"))
    )
    (comp (ref "D224")
      (value "1N4148DO35-10")
      (footprint "eagle-import:DO35-10")
      (libsource (lib "eagle-import") (part "1N4148DO35-10"))
    )
    (comp (ref "D225")
      (value "1N4148DO35-10")
      (footprint "eagle-import:DO35-10")
      (libsource (lib "eagle-import") (part "1N4148DO35-10"))
    )
    (comp (ref "D226")
      (value "1N4148DO35-10")
      (footprint "eagle-import:DO35-10")
      (libsource (lib "eagle-import") (part "1N4148DO35-10"))
    )
    (comp (ref "D227")
      (value "1N4148DO35-10")
      (footprint "eagle-import:DO35-10")
      (libsource (lib "eagle-import") (part "1N4148DO35-10"))
    )
    (comp (ref "D228")
      (value "1N4148DO35-10")
      (footprint "eagle-import:DO35-10")
      (libsource (lib "eagle-import") (part "1N4148DO35-10"))
    )
    (comp (ref "D229")
      (value "1N4148DO35-10")
      (footprint "eagle-import:DO35-10")
      (libsource (lib "eagle-import") (part "1N4148DO35-10"))
    )
    (comp (ref "D230")
      (value "1N4148DO35-10")
      (footprint "eagle-import:DO35-10")
      (libsource (lib "eagle-import") (part "1N4148DO35-10"))
    )
    (comp (ref "D231")
      (value "1N4148DO35-10")
      (footprint "eagle-import:DO35-10")
      (libsource (lib "eagle-import") (part "1N4148DO35-10"))
    )
    (comp (ref "D232")
      (value "1N4148DO35-10")
      (footprint "eagle-import:DO35-10")
      (libsource (lib "eagle-import") (part "1N4148DO35-10"))
    )
    (comp (ref "D233")
      (value "1N4148DO35-10")
      (footprint "eagle-import:DO35-10")
      (libsource (lib "eagle-import") (part "1N4148DO35-10"))
    )
    (comp (ref "D234")
      (value "1N4148DO35-10")
      (footprint "eagle-import:DO35-10")
      (libsource (lib "eagle-import") (part "1N4148DO35-10"))
    )
    (comp (ref "D235")
      (value "1N4148DO35-10")
      (footprint "eagle-import:DO35-10")
      (libsource (lib "eagle-import") (part "1N4148DO35-10"))
    )
    (comp (ref "D236")
      (value "1N4148DO35-10")
      (footprint "eagle-import:DO35-10")
      (libsource (lib "eagle-import") (part "1N4148DO35-10"))
    )
    (comp (ref "D237")
      (value "1N4148DO35-10")
      (footprint "eagle-import:DO35-10")
      (libsource (lib "eagle-import") (part "1N4148DO35-10"))
    )
    (comp (ref "D238")
      (value "1N4148DO35-10")
      (footprint "eagle-import:DO35-10")
      (libsource (lib "eagle-import") (part "1N4148DO35-10"))
    )
    (comp (ref "D239")
      (value "1N4148DO35-10")
      (footprint "eagle-import:DO35-10")
      (libsource (lib "eagle-import") (part "1N4148DO35-10"))
    )
    (comp (ref "D240")
      (value "1N4148DO35-10")
      (footprint "eagle-import:DO35-10")
      (libsource (lib "eagle-import") (part "1N4148DO35-10"))
    )
    (comp (ref "D241")
      (value "1N4148DO35-10")
      (footprint "eagle-import:DO35-10")
      (libsource (lib "eagle-import") (part "1N4148DO35-10"))
    )
    (comp (ref "D242")
      (value "1N4148DO35-10")
      (footprint "eagle-import:DO35-10")
      (libsource (lib "eagle-import") (part "1N4148DO35-10"))
    )
    (comp (ref "D243")
      (value "1N4148DO35-10")
      (footprint "eagle-import:DO35-10")
      (libsource (lib "eagle-import") (part "1N4148DO35-10"))
    )
    (comp (ref "D244")
      (value "1N4148DO35-10")
      (footprint "eagle-import:DO35-10")
      (libsource (lib "eagle-import") (part "1N4148DO35-10"))
    )
    (comp (ref "D245")
      (value "1N4148DO35-10")
      (footprint "eagle-import:DO35-10")
      (libsource (lib "eagle-import") (part "1N4148DO35-10"))
    )
    (comp (ref "D246")
      (value "1N4148DO35-10")
      (footprint "eagle-import:DO35-10")
      (libsource (lib "eagle-import") (part "1N4148DO35-10"))
    )
    (comp (ref "D247")
      (value "1N4148DO35-10")
      (footprint "eagle-import:DO35-10")
      (libsource (lib "eagle-import") (part "1N4148DO35-10"))
    )
    (comp (ref "D248")
      (value "1N4148DO35-10")
      (footprint "eagle-import:DO35-10")
      (libsource (lib "eagle-import") (part "1N4148DO35-10"))
    )
    (comp (ref "D249")
      (value "1N4148DO35-10")
      (footprint "eagle-import:DO35-10")
      (libsource (lib "eagle-import") (part "1N4148DO35-10"))
    )
    (comp (ref "D250")
      (value "1N4148DO35-10")
      (footprint "eagle-import:DO35-10")
      (libsource (lib "eagle-import") (part "1N4148DO35-10"))
    )
    (comp (ref "D251")
      (value "1N4148DO35-10")
      (footprint "eagle-import:DO35-10")
      (libsource (lib "eagle-import") (part "1N4148DO35-10"))
    )
    (comp (ref "D252")
      (value "1N4148DO35-10")
      (footprint "eagle-import:DO35-10")
      (libsource (lib "eagle-import") (part "1N4148DO35-10"))
    )
    (comp (ref "D253")
      (value "1N4148DO35-10")
      (footprint "eagle-import:DO35-10")
      (libsource (lib "eagle-import") (part "1N4148DO35-10"))
    )
    (comp (ref "D254")
      (value "1N4148DO35-10")
      (footprint "eagle-import:DO35-10")
      (libsource (lib "eagle-import") (part "1N4148DO35-10"))
    )
    (comp (ref "D255")
      (value "1N4148DO35-10")
      (footprint "eagle-import:DO35-10")
      (libsource (lib "eagle-import") (part "1N4148DO35-10"))
    )
    (comp (ref "D256")
      (value "1N4148DO35-10")
      (footprint "eagle-import:DO35-10")
      (libsource (lib "eagle-import") (part "1N4148DO35-10"))
    )
    (comp (ref "D257")
      (value "1N4148DO35-10")
      (footprint "eagle-import:DO35-10")
      (libsource (lib "eagle-import") (part "1N4148DO35-10"))
    )
    (comp (ref "D258")
      (value "1N4148DO35-10")
      (footprint "eagle-import:DO35-10")
      (libsource (lib "eagle-import") (part "1N4148DO35-10"))
    )
    (comp (ref "D259")
      (value "1N4148DO35-10")
      (footprint "eagle-import:DO35-10")
      (libsource (lib "eagle-import") (part "1N4148DO35-10"))
    )
    (comp (ref "D260")
      (value "1N4148DO35-10")
      (footprint "eagle-import:DO35-10")
      (libsource (lib "eagle-import") (part "1N4148DO35-10"))
    )
    (comp (ref "D261")
      (value "1N4148DO35-10")
      (footprint "eagle-import:DO35-10")
      (libsource (lib "eagle-import") (part "1N4148DO35-10"))
    )
    (comp (ref "D262")
      (value "1N4148DO35-10")
      (footprint "eagle-import:DO35-10")
      (libsource (lib "eagle-import") (part "1N4148DO35-10"))
    )
    (comp (ref "D263")
      (value "1N4148DO35-10")
      (footprint "eagle-import:DO35-10")
      (libsource (lib "eagle-import") (part "1N4148DO35-10"))
    )
    (comp (ref "D264")
      (value "1N4148DO35-10")
      (footprint "eagle-import:DO35-10")
      (libsource (lib "eagle-import") (part "1N4148DO35-10"))
    )
    (comp (ref "D265")
      (value "1N4148DO35-10")
      (footprint "eagle-import:DO35-10")
      (libsource (lib "eagle-import") (part "1N4148DO35-10"))
    )
    (comp (ref "D266")
      (value "1N4148DO35-10")
      (footprint "eagle-import:DO35-10")
      (libsource (lib "eagle-import") (part "1N4148DO35-10"))
    )
    (comp (ref "D267")
      (value "1N4148DO35-10")
      (footprint "eagle-import:DO35-10")
      (libsource (lib "eagle-import") (part "1N4148DO35-10"))
    )
    (comp (ref "D268")
      (value "1N4148DO35-10")
      (footprint "eagle-import:DO35-10")
      (libsource (lib "eagle-import") (part "1N4148DO35-10"))
    )
    (comp (ref "D269")
      (value "1N4148DO35-10")
      (footprint "eagle-import:DO35-10")
      (libsource (lib "eagle-import") (part "1N4148DO35-10"))
    )
    (comp (ref "D270")
      (value "1N4148DO35-10")
      (footprint "eagle-import:DO35-10")
      (libsource (lib "eagle-import") (part "1N4148DO35-10"))
    )
    (comp (ref "D271")
      (value "1N4148DO35-10")
      (footprint "eagle-import:DO35-10")
      (libsource (lib "eagle-import") (part "1N4148DO35-10"))
    )
    (comp (ref "D272")
      (value "1N4148DO35-10")
      (footprint "eagle-import:DO35-10")
      (libsource (lib "eagle-import") (part "1N4148DO35-10"))
    )
    (comp (ref "D273")
      (value "1N4148DO35-10")
      (footprint "eagle-import:DO35-10")
      (libsource (lib "eagle-import") (part "1N4148DO35-10"))
    )
    (comp (ref "D274")
      (value "1N4148DO35-10")
      (footprint "eagle-import:DO35-10")
      (libsource (lib "eagle-import") (part "1N4148DO35-10"))
    )
    (comp (ref "D275")
      (value "1N4148DO35-10")
      (footprint "eagle-import:DO35-10")
      (libsource (lib "eagle-import") (part "1N4148DO35-10"))
    )
    (comp (ref "D276")
      (value "1N4148DO35-10")
      (footprint "eagle-import:DO35-10")
      (libsource (lib "eagle-import") (part "1N4148DO35-10"))
    )
    (comp (ref "D277")
      (value "1N4148DO35-10")
      (footprint "eagle-import:DO35-10")
      (libsource (lib "eagle-import") (part "1N4148DO35-10"))
    )
    (comp (ref "D278")
      (value "1N4148DO35-10")
      (footprint "eagle-import:DO35-10")
      (libsource (lib "eagle-import") (part "1N4148DO35-10"))
    )
    (comp (ref "D279")
      (value "1N4148DO35-10")
      (footprint "eagle-import:DO35-10")
      (libsource (lib "eagle-import") (part "1N4148DO35-10"))
    )
    (comp (ref "D280")
      (value "1N4148DO35-10")
      (footprint "eagle-import:DO35-10")
      (libsource (lib "eagle-import") (part "1N4148DO35-10"))
    )
    (comp (ref "D281")
      (value "1N4148DO35-10")
      (footprint "eagle-import:DO35-10")
      (libsource (lib "eagle-import") (part "1N4148DO35-10"))
    )
    (comp (ref "D282")
      (value "1N4148DO35-10")
      (footprint "eagle-import:DO35-10")
      (libsource (lib "eagle-import") (part "1N4148DO35-10"))
    )
    (comp (ref "D283")
      (value "1N4148DO35-10")
      (footprint "eagle-import:DO35-10")
      (libsource (lib "eagle-import") (part "1N4148DO35-10"))
    )
    (comp (ref "D284")
      (value "1N4148DO35-10")
      (footprint "eagle-import:DO35-10")
      (libsource (lib "eagle-import") (part "1N4148DO35-10"))
    )
    (comp (ref "D285")
      (value "1N4148DO35-10")
      (footprint "eagle-import:DO35-10")
      (libsource (lib "eagle-import") (part "1N4148DO35-10"))
    )
    (comp (ref "D286")
      (value "1N4148DO35-10")
      (footprint "eagle-import:DO35-10")
      (libsource (lib "eagle-import") (part "1N4148DO35-10"))
    )
    (comp (ref "D287")
      (value "1N4148DO35-10")
      (footprint "eagle-import:DO35-10")
      (libsource (lib "eagle-import") (part "1N4148DO35-10"))
    )
    (comp (ref "D288")
      (value "1N4148DO35-10")
      (footprint "eagle-import:DO35-10")
      (libsource (lib "eagle-import") (part "1N4148DO35-10"))
    )
    (comp (ref "D289")
      (value "1N4148DO35-10")
      (footprint "eagle-import:DO35-10")
      (libsource (lib "eagle-import") (part "1N4148DO35-10"))
    )
    (comp (ref "D290")
      (value "1N4148DO35-10")
      (footprint "eagle-import:DO35-10")
      (libsource (lib "eagle-import") (part "1N4148DO35-10"))
    )
    (comp (ref "D291")
      (value "1N4148DO35-10")
      (footprint "eagle-import:DO35-10")
      (libsource (lib "eagle-import") (part "1N4148DO35-10"))
    )
    (comp (ref "D292")
      (value "1N4148DO35-10")
      (footprint "eagle-import:DO35-10")
      (libsource (lib "eagle-import") (part "1N4148DO35-10"))
    )
    (comp (ref "D293")
      (value "1N4148DO35-10")
      (footprint "eagle-import:DO35-10")
      (libsource (lib "eagle-import") (part "1N4148DO35-10"))
    )
    (comp (ref "D294")
      (value "1N4148DO35-10")
      (footprint "eagle-import:DO35-10")
      (libsource (lib "eagle-import") (part "1N4148DO35-10"))
    )
    (comp (ref "D295")
      (value "1N4148DO35-10")
      (footprint "eagle-import:DO35-10")
      (libsource (lib "eagle-import") (part "1N4148DO35-10"))
    )
    (comp (ref "D296")
      (value "1N4148DO35-10")
      (footprint "eagle-import:DO35-10")
      (libsource (lib "eagle-import") (part "1N4148DO35-10"))
    )
    (comp (ref "D297")
      (value "1N4148DO35-10")
      (footprint "eagle-import:DO35-10")
      (libsource (lib "eagle-import") (part "1N4148DO35-10"))
    )
    (comp (ref "D298")
      (value "1N4148DO35-10")
      (footprint "eagle-import:DO35-10")
      (libsource (lib "eagle-import") (part "1N4148DO35-10"))
    )
    (comp (ref "D299")
      (value "1N4148DO35-10")
      (footprint "eagle-import:DO35-10")
      (libsource (lib "eagle-import") (part "1N4148DO35-10"))
    )
    (comp (ref "D300")
      (value "1N4148DO35-10")
      (footprint "eagle-import:DO35-10")
      (libsource (lib "eagle-import") (part "1N4148DO35-10"))
    )
    (comp (ref "D301")
      (value "1N4148DO35-10")
      (footprint "eagle-import:DO35-10")
      (libsource (lib "eagle-import") (part "1N4148DO35-10"))
    )
    (comp (ref "D302")
      (value "1N4148DO35-10")
      (footprint "eagle-import:DO35-10")
      (libsource (lib "eagle-import") (part "1N4148DO35-10"))
    )
    (comp (ref "D303")
      (value "1N4148DO35-10")
      (footprint "eagle-import:DO35-10")
      (libsource (lib "eagle-import") (part "1N4148DO35-10"))
    )
    (comp (ref "D304")
      (value "1N4148DO35-10")
      (footprint "eagle-import:DO35-10")
      (libsource (lib "eagle-import") (part "1N4148DO35-10"))
    )
    (comp (ref "D305")
      (value "1N4148DO35-10")
      (footprint "eagle-import:DO35-10")
      (libsource (lib "eagle-import") (part "1N4148DO35-10"))
    )
    (comp (ref "D306")
      (value "1N4148DO35-10")
      (footprint "eagle-import:DO35-10")
      (libsource (lib "eagle-import") (part "1N4148DO35-10"))
    )
    (comp (ref "D307")
      (value "1N4148DO35-10")
      (footprint "eagle-import:DO35-10")
      (libsource (lib "eagle-import") (part "1N4148DO35-10"))
    )
    (comp (ref "D308")
      (value "1N4148DO35-10")
      (footprint "eagle-import:DO35-10")
      (libsource (lib "eagle-import") (part "1N4148DO35-10"))
    )
    (comp (ref "D309")
      (value "1N4148DO35-10")
      (footprint "eagle-import:DO35-10")
      (libsource (lib "eagle-import") (part "1N4148DO35-10"))
    )
    (comp (ref "D310")
      (value "1N4148DO35-10")
      (footprint "eagle-import:DO35-10")
      (libsource (lib "eagle-import") (part "1N4148DO35-10"))
    )
    (comp (ref "D311")
      (value "1N4148DO35-10")
      (footprint "eagle-import:DO35-10")
      (libsource (lib "eagle-import") (part "1N4148DO35-10"))
    )
    (comp (ref "D312")
      (value "1N4148DO35-10")
      (footprint "eagle-import:DO35-10")
      (libsource (lib "eagle-import") (part "1N4148DO35-10"))
    )
    (comp (ref "D313")
      (value "1N4148DO35-10")
      (footprint "eagle-import:DO35-10")
      (libsource (lib "eagle-import") (part "1N4148DO35-10"))
    )
    (comp (ref "D314")
      (value "1N4148DO35-10")
      (footprint "eagle-import:DO35-10")
      (libsource (lib "eagle-import") (part "1N4148DO35-10"))
    )
    (comp (ref "D315")
      (value "1N4148DO35-10")
      (footprint "eagle-import:DO35-10")
      (libsource (lib "eagle-import") (part "1N4148DO35-10"))
    )
    (comp (ref "D316")
      (value "1N4148DO35-10")
      (footprint "eagle-import:DO35-10")
      (libsource (lib "eagle-import") (part "1N4148DO35-10"))
    )
    (comp (ref "D317")
      (value "1N4148DO35-10")
      (footprint "eagle-import:DO35-10")
      (libsource (lib "eagle-import") (part "1N4148DO35-10"))
    )
    (comp (ref "D318")
      (value "1N4148DO35-10")
      (footprint "eagle-import:DO35-10")
      (libsource (lib "eagle-import") (part "1N4148DO35-10"))
    )
    (comp (ref "D319")
      (value "1N4148DO35-10")
      (footprint "eagle-import:DO35-10")
      (libsource (lib "eagle-import") (part "1N4148DO35-10"))
    )
    (comp (ref "D320")
      (value "1N4148DO35-10")
      (footprint "eagle-import:DO35-10")
      (libsource (lib "eagle-import") (part "1N4148DO35-10"))
    )
    (comp (ref "D321")
      (value "1N4148DO35-10")
      (footprint "eagle-import:DO35-10")
      (libsource (lib "eagle-import") (part "1N4148DO35-10"))
    )
    (comp (ref "D322")
      (value "1N4148DO35-10")
      (footprint "eagle-import:DO35-10")
      (libsource (lib "eagle-import") (part "1N4148DO35-10"))
    )
    (comp (ref "D323")
      (value "1N4148DO35-10")
      (footprint "eagle-import:DO35-10")
      (libsource (lib "eagle-import") (part "1N4148DO35-10"))
    )
    (comp (ref "D324")
      (value "1N4148DO35-10")
      (footprint "eagle-import:DO35-10")
      (libsource (lib "eagle-import") (part "1N4148DO35-10"))
    )
    (comp (ref "D325")
      (value "1N4148DO35-10")
      (footprint "eagle-import:DO35-10")
      (libsource (lib "eagle-import") (part "1N4148DO35-10"))
    )
    (comp (ref "D326")
      (value "1N4148DO35-10")
      (footprint "eagle-import:DO35-10")
      (libsource (lib "eagle-import") (part "1N4148DO35-10"))
    )
    (comp (ref "D327")
      (value "1N4148DO35-10")
      (footprint "eagle-import:DO35-10")
      (libsource (lib "eagle-import") (part "1N4148DO35-10"))
    )
    (comp (ref "D328")
      (value "1N4148DO35-10")
      (footprint "eagle-import:DO35-10")
      (libsource (lib "eagle-import") (part "1N4148DO35-10"))
    )
    (comp (ref "D329")
      (value "1N4148DO35-10")
      (footprint "eagle-import:DO35-10")
      (libsource (lib "eagle-import") (part "1N4148DO35-10"))
    )
    (comp (ref "D330")
      (value "1N4148DO35-10")
      (footprint "eagle-import:DO35-10")
      (libsource (lib "eagle-import") (part "1N4148DO35-10"))
    )
    (comp (ref "D331")
      (value "1N4148DO35-10")
      (footprint "eagle-import:DO35-10")
      (libsource (lib "eagle-import") (part "1N4148DO35-10"))
    )
    (comp (ref "D332")
      (value "1N4148DO35-10")
      (footprint "eagle-import:DO35-10")
      (libsource (lib "eagle-import") (part "1N4148DO35-10"))
    )
    (comp (ref "D333")
      (value "1N4148DO35-10")
      (footprint "eagle-import:DO35-10")
      (libsource (lib "eagle-import") (part "1N4148DO35-10"))
    )
    (comp (ref "D334")
      (value "1N4148DO35-10")
      (footprint "eagle-import:DO35-10")
      (libsource (lib "eagle-import") (part "1N4148DO35-10"))
    )
    (comp (ref "D335")
      (value "1N4148DO35-10")
      (footprint "eagle-import:DO35-10")
      (libsource (lib "eagle-import") (part "1N4148DO35-10"))
    )
    (comp (ref "D336")
      (value "1N4148DO35-10")
      (footprint "eagle-import:DO35-10")
      (libsource (lib "eagle-import") (part "1N4148DO35-10"))
    )
    (comp (ref "D337")
      (value "1N4148DO35-10")
      (footprint "eagle-import:DO35-10")
      (libsource (lib "eagle-import") (part "1N4148DO35-10"))
    )
    (comp (ref "D338")
      (value "1N4148DO35-10")
      (footprint "eagle-import:DO35-10")
      (libsource (lib "eagle-import") (part "1N4148DO35-10"))
    )
    (comp (ref "D339")
      (value "1N4148DO35-10")
      (footprint "eagle-import:DO35-10")
      (libsource (lib "eagle-import") (part "1N4148DO35-10"))
    )
    (comp (ref "D340")
      (value "1N4148DO35-10")
      (footprint "eagle-import:DO35-10")
      (libsource (lib "eagle-import") (part "1N4148DO35-10"))
    )
    (comp (ref "D341")
      (value "1N4148DO35-10")
      (footprint "eagle-import:DO35-10")
      (libsource (lib "eagle-import") (part "1N4148DO35-10"))
    )
    (comp (ref "D342")
      (value "1N4148DO35-10")
      (footprint "eagle-import:DO35-10")
      (libsource (lib "eagle-import") (part "1N4148DO35-10"))
    )
    (comp (ref "D343")
      (value "1N4148DO35-10")
      (footprint "eagle-import:DO35-10")
      (libsource (lib "eagle-import") (part "1N4148DO35-10"))
    )
    (comp (ref "D344")
      (value "1N4148DO35-10")
      (footprint "eagle-import:DO35-10")
      (libsource (lib "eagle-import") (part "1N4148DO35-10"))
    )
    (comp (ref "D345")
      (value "1N4148DO35-10")
      (footprint "eagle-import:DO35-10")
      (libsource (lib "eagle-import") (part "1N4148DO35-10"))
    )
    (comp (ref "D346")
      (value "1N4148DO35-10")
      (footprint "eagle-import:DO35-10")
      (libsource (lib "eagle-import") (part "1N4148DO35-10"))
    )
    (comp (ref "D347")
      (value "1N4148DO35-10")
      (footprint "eagle-import:DO35-10")
      (libsource (lib "eagle-import") (part "1N4148DO35-10"))
    )
    (comp (ref "D348")
      (value "1N4148DO35-10")
      (footprint "eagle-import:DO35-10")
      (libsource (lib "eagle-import") (part "1N4148DO35-10"))
    )
    (comp (ref "D349")
      (value "1N4148DO35-10")
      (footprint "eagle-import:DO35-10")
      (libsource (lib "eagle-import") (part "1N4148DO35-10"))
    )
    (comp (ref "D350")
      (value "1N4148DO35-10")
      (footprint "eagle-import:DO35-10")
      (libsource (lib "eagle-import") (part "1N4148DO35-10"))
    )
    (comp (ref "D351")
      (value "1N4148DO35-10")
      (footprint "eagle-import:DO35-10")
      (libsource (lib "eagle-import") (part "1N4148DO35-10"))
    )
    (comp (ref "D352")
      (value "1N4148DO35-10")
      (footprint "eagle-import:DO35-10")
      (libsource (lib "eagle-import") (part "1N4148DO35-10"))
    )
    (comp (ref "D353")
      (value "1N4148DO35-10")
      (footprint "eagle-import:DO35-10")
      (libsource (lib "eagle-import") (part "1N4148DO35-10"))
    )
    (comp (ref "D354")
      (value "1N4148DO35-10")
      (footprint "eagle-import:DO35-10")
      (libsource (lib "eagle-import") (part "1N4148DO35-10"))
    )
    (comp (ref "D355")
      (value "1N4148DO35-10")
      (footprint "eagle-import:DO35-10")
      (libsource (lib "eagle-import") (part "1N4148DO35-10"))
    )
    (comp (ref "D356")
      (value "1N4148DO35-10")
      (footprint "eagle-import:DO35-10")
      (libsource (lib "eagle-import") (part "1N4148DO35-10"))
    )
    (comp (ref "D357")
      (value "1N4148DO35-10")
      (footprint "eagle-import:DO35-10")
      (libsource (lib "eagle-import") (part "1N4148DO35-10"))
    )
    (comp (ref "D358")
      (value "1N4148DO35-10")
      (footprint "eagle-import:DO35-10")
      (libsource (lib "eagle-import") (part "1N4148DO35-10"))
    )
    (comp (ref "D359")
      (value "1N4148DO35-10")
      (footprint "eagle-import:DO35-10")
      (libsource (lib "eagle-import") (part "1N4148DO35-10"))
    )
    (comp (ref "D360")
      (value "1N4148DO35-10")
      (footprint "eagle-import:DO35-10")
      (libsource (lib "eagle-import") (part "1N4148DO35-10"))
    )
    (comp (ref "D361")
      (value "1N4148DO35-10")
      (footprint "eagle-import:DO35-10")
      (libsource (lib "eagle-import") (part "1N4148DO35-10"))
    )
    (comp (ref "D362")
      (value "1N4148DO35-10")
      (footprint "eagle-import:DO35-10")
      (libsource (lib "eagle-import") (part "1N4148DO35-10"))
    )
    (comp (ref "D363")
      (value "1N4148DO35-10")
      (footprint "eagle-import:DO35-10")
      (libsource (lib "eagle-import") (part "1N4148DO35-10"))
    )
    (comp (ref "D364")
      (value "1N4148DO35-10")
      (footprint "eagle-import:DO35-10")
      (libsource (lib "eagle-import") (part "1N4148DO35-10"))
    )
    (comp (ref "D365")
      (value "1N4148DO35-10")
      (footprint "eagle-import:DO35-10")
      (libsource (lib "eagle-import") (part "1N4148DO35-10"))
    )
    (comp (ref "D366")
      (value "1N4148DO35-10")
      (footprint "eagle-import:DO35-10")
      (libsource (lib "eagle-import") (part "1N4148DO35-10"))
    )
    (comp (ref "D367")
      (value "1N4148DO35-10")
      (footprint "eagle-import:DO35-10")
      (libsource (lib "eagle-import") (part "1N4148DO35-10"))
    )
    (comp (ref "D368")
      (value "1N4148DO35-10")
      (footprint "eagle-import:DO35-10")
      (libsource (lib "eagle-import") (part "1N4148DO35-10"))
    )
    (comp (ref "D369")
      (value "1N4148DO35-10")
      (footprint "eagle-import:DO35-10")
      (libsource (lib "eagle-import") (part "1N4148DO35-10"))
    )
    (comp (ref "D370")
      (value "1N4148DO35-10")
      (footprint "eagle-import:DO35-10")
      (libsource (lib "eagle-import") (part "1N4148DO35-10"))
    )
    (comp (ref "D371")
      (value "1N4148DO35-10")
      (footprint "eagle-import:DO35-10")
      (libsource (lib "eagle-import") (part "1N4148DO35-10"))
    )
    (comp (ref "D372")
      (value "1N4148DO35-10")
      (footprint "eagle-import:DO35-10")
      (libsource (lib "eagle-import") (part "1N4148DO35-10"))
    )
    (comp (ref "D373")
      (value "1N4148DO35-10")
      (footprint "eagle-import:DO35-10")
      (libsource (lib "eagle-import") (part "1N4148DO35-10"))
    )
    (comp (ref "D374")
      (value "1N4148DO35-10")
      (footprint "eagle-import:DO35-10")
      (libsource (lib "eagle-import") (part "1N4148DO35-10"))
    )
    (comp (ref "D375")
      (value "1N4148DO35-10")
      (footprint "eagle-import:DO35-10")
      (libsource (lib "eagle-import") (part "1N4148DO35-10"))
    )
    (comp (ref "D376")
      (value "1N4148DO35-10")
      (footprint "eagle-import:DO35-10")
      (libsource (lib "eagle-import") (part "1N4148DO35-10"))
    )
    (comp (ref "D377")
      (value "1N4148DO35-10")
      (footprint "eagle-import:DO35-10")
      (libsource (lib "eagle-import") (part "1N4148DO35-10"))
    )
    (comp (ref "D378")
      (value "1N4148DO35-10")
      (footprint "eagle-import:DO35-10")
      (libsource (lib "eagle-import") (part "1N4148DO35-10"))
    )
    (comp (ref "D379")
      (value "1N4148DO35-10")
      (footprint "eagle-import:DO35-10")
      (libsource (lib "eagle-import") (part "1N4148DO35-10"))
    )
    (comp (ref "D380")
      (value "1N4148DO35-10")
      (footprint "eagle-import:DO35-10")
      (libsource (lib "eagle-import") (part "1N4148DO35-10"))
    )
    (comp (ref "D381")
      (value "1N4148DO35-10")
      (footprint "eagle-import:DO35-10")
      (libsource (lib "eagle-import") (part "1N4148DO35-10"))
    )
    (comp (ref "D382")
      (value "1N4148DO35-10")
      (footprint "eagle-import:DO35-10")
      (libsource (lib "eagle-import") (part "1N4148DO35-10"))
    )
    (comp (ref "D383")
      (value "1N4148DO35-10")
      (footprint "eagle-import:DO35-10")
      (libsource (lib "eagle-import") (part "1N4148DO35-10"))
    )
    (comp (ref "D384")
      (value "1N4148DO35-10")
      (footprint "eagle-import:DO35-10")
      (libsource (lib "eagle-import") (part "1N4148DO35-10"))
    )
    (comp (ref "E1")
      (value "SP384N")
      (footprint "eagle-import:DIL14")
      (libsource (lib "eagle-import") (part "SP384N"))
    )
    (comp (ref "E4")
      (value "N8881N")
      (footprint "eagle-import:DIL14")
      (libsource (lib "eagle-import") (part "N8881N"))
    )
    (comp (ref "E14")
      (value "N8881N")
      (footprint "eagle-import:DIL14")
      (libsource (lib "eagle-import") (part "N8881N"))
    )
    (comp (ref "E17")
      (value "SP384N")
      (footprint "eagle-import:DIL14")
      (libsource (lib "eagle-import") (part "SP384N"))
    )
    (comp (ref "E43")
      (value "SP384N")
      (footprint "eagle-import:DIL14")
      (libsource (lib "eagle-import") (part "SP384N"))
    )
    (comp (ref "IC7")
      (value "N8881N")
      (footprint "eagle-import:DIL14")
      (libsource (lib "eagle-import") (part "N8881N"))
    )
    (comp (ref "U$1")
      (value "OUTLINE-OMNIBUS")
      (footprint "eagle-import:OMNIBUS")
      (libsource (lib "eagle-import") (part "OUTLINE-OMNIBUS"))
    )
    (comp (ref "U$2")
      (value "QUAD")
      (footprint "eagle-import:EDGE-CON8")
      (libsource (lib "eagle-import") (part "QUAD"))
    )
    (comp (ref "E3")
      (value "7404N")
      (footprint "eagle-import:DIL14")
      (libsource (lib "eagle-import") (part "7404N"))
    )
    (comp (ref "E6")
      (value "74164N")
      (footprint "eagle-import:DIL14")
      (libsource (lib "eagle-import") (part "74164N"))
    )
    (comp (ref "E8")
      (value "7404N")
      (footprint "eagle-import:DIL14")
      (libsource (lib "eagle-import") (part "7404N"))
    )
    (comp (ref "E9")
      (value "74164N")
      (footprint "eagle-import:DIL14")
      (libsource (lib "eagle-import") (part "74164N"))
    )
    (comp (ref "E10")
      (value "7404N")
      (footprint "eagle-import:DIL14")
      (libsource (lib "eagle-import") (part "7404N"))
    )
    (comp (ref "E24")
      (value "7404N")
      (footprint "eagle-import:DIL14")
      (libsource (lib "eagle-import") (part "7404N"))
    )
    (comp (ref "E25")
      (value "74164N")
      (footprint "eagle-import:DIL14")
      (libsource (lib "eagle-import") (part "74164N"))
    )
    (comp (ref "E27")
      (value "SP380N")
      (footprint "eagle-import:DIL14")
      (libsource (lib "eagle-import") (part "SP380N"))
    )
    (comp (ref "E28")
      (value "7404N")
      (footprint "eagle-import:DIL14")
      (libsource (lib "eagle-import") (part "7404N"))
    )
    (comp (ref "E31")
      (value "74164N")
      (footprint "eagle-import:DIL14")
      (libsource (lib "eagle-import") (part "74164N"))
    )
    (comp (ref "E34")
      (value "7404N")
      (footprint "eagle-import:DIL14")
      (libsource (lib "eagle-import") (part "7404N"))
    )
  )
  (nets
    (net (code "1") (name "-15V") (class "Default")
      (node (ref "U$2") (pin "DB2") (pinfunction "1_DB2") (pintype "bidirectional"))
    )
    (net (code "2") (name "C01") (class "Default")
      (node (ref "D1") (pin "C") (pinfunction "C_C") (pintype "passive"))
      (node (ref "D10") (pin "C") (pinfunction "C_C") (pintype "passive"))
      (node (ref "D11") (pin "C") (pinfunction "C_C") (pintype "passive"))
      (node (ref "D12") (pin "C") (pinfunction "C_C") (pintype "passive"))
      (node (ref "D2") (pin "C") (pinfunction "C_C") (pintype "passive"))
      (node (ref "D3") (pin "C") (pinfunction "C_C") (pintype "passive"))
      (node (ref "D4") (pin "C") (pinfunction "C_C") (pintype "passive"))
      (node (ref "D5") (pin "C") (pinfunction "C_C") (pintype "passive"))
      (node (ref "D6") (pin "C") (pinfunction "C_C") (pintype "passive"))
      (node (ref "D7") (pin "C") (pinfunction "C_C") (pintype "passive"))
      (node (ref "D8") (pin "C") (pinfunction "C_C") (pintype "passive"))
      (node (ref "D9") (pin "C") (pinfunction "C_C") (pintype "passive"))
      (node (ref "E34") (pin "6") (pinfunction "O_6") (pintype "output"))
    )
    (net (code "3") (name "C02") (class "Default")
      (node (ref "D13") (pin "C") (pinfunction "C_C") (pintype "passive"))
      (node (ref "D14") (pin "C") (pinfunction "C_C") (pintype "passive"))
      (node (ref "D15") (pin "C") (pinfunction "C_C") (pintype "passive"))
      (node (ref "D16") (pin "C") (pinfunction "C_C") (pintype "passive"))
      (node (ref "D17") (pin "C") (pinfunction "C_C") (pintype "passive"))
      (node (ref "D18") (pin "C") (pinfunction "C_C") (pintype "passive"))
      (node (ref "D19") (pin "C") (pinfunction "C_C") (pintype "passive"))
      (node (ref "D20") (pin "C") (pinfunction "C_C") (pintype "passive"))
      (node (ref "D21") (pin "C") (pinfunction "C_C") (pintype "passive"))
      (node (ref "D22") (pin "C") (pinfunction "C_C") (pintype "passive"))
      (node (ref "D23") (pin "C") (pinfunction "C_C") (pintype "passive"))
      (node (ref "D24") (pin "C") (pinfunction "C_C") (pintype "passive"))
      (node (ref "E34") (pin "4") (pinfunction "O_4") (pintype "output"))
    )
    (net (code "4") (name "C03") (class "Default")
      (node (ref "D25") (pin "C") (pinfunction "C_C") (pintype "passive"))
      (node (ref "D26") (pin "C") (pinfunction "C_C") (pintype "passive"))
      (node (ref "D27") (pin "C") (pinfunction "C_C") (pintype "passive"))
      (node (ref "D28") (pin "C") (pinfunction "C_C") (pintype "passive"))
      (node (ref "D29") (pin "C") (pinfunction "C_C") (pintype "passive"))
      (node (ref "D30") (pin "C") (pinfunction "C_C") (pintype "passive"))
      (node (ref "D31") (pin "C") (pinfunction "C_C") (pintype "passive"))
      (node (ref "D32") (pin "C") (pinfunction "C_C") (pintype "passive"))
      (node (ref "D33") (pin "C") (pinfunction "C_C") (pintype "passive"))
      (node (ref "D34") (pin "C") (pinfunction "C_C") (pintype "passive"))
      (node (ref "D35") (pin "C") (pinfunction "C_C") (pintype "passive"))
      (node (ref "D36") (pin "C") (pinfunction "C_C") (pintype "passive"))
      (node (ref "E34") (pin "2") (pinfunction "O_2") (pintype "output"))
    )
    (net (code "5") (name "C04") (class "Default")
      (node (ref "D37") (pin "C") (pinfunction "C_C") (pintype "passive"))
      (node (ref "D38") (pin "C") (pinfunction "C_C") (pintype "passive"))
      (node (ref "D39") (pin "C") (pinfunction "C_C") (pintype "passive"))
      (node (ref "D40") (pin "C") (pinfunction "C_C") (pintype "passive"))
      (node (ref "D41") (pin "C") (pinfunction "C_C") (pintype "passive"))
      (node (ref "D42") (pin "C") (pinfunction "C_C") (pintype "passive"))
      (node (ref "D43") (pin "C") (pinfunction "C_C") (pintype "passive"))
      (node (ref "D44") (pin "C") (pinfunction "C_C") (pintype "passive"))
      (node (ref "D45") (pin "C") (pinfunction "C_C") (pintype "passive"))
      (node (ref "D46") (pin "C") (pinfunction "C_C") (pintype "passive"))
      (node (ref "D47") (pin "C") (pinfunction "C_C") (pintype "passive"))
      (node (ref "D48") (pin "C") (pinfunction "C_C") (pintype "passive"))
      (node (ref "E34") (pin "12") (pinfunction "O_12") (pintype "output"))
    )
    (net (code "6") (name "C05") (class "Default")
      (node (ref "D49") (pin "C") (pinfunction "C_C") (pintype "passive"))
      (node (ref "D50") (pin "C") (pinfunction "C_C") (pintype "passive"))
      (node (ref "D51") (pin "C") (pinfunction "C_C") (pintype "passive"))
      (node (ref "D52") (pin "C") (pinfunction "C_C") (pintype "passive"))
      (node (ref "D53") (pin "C") (pinfunction "C_C") (pintype "passive"))
      (node (ref "D54") (pin "C") (pinfunction "C_C") (pintype "passive"))
      (node (ref "D55") (pin "C") (pinfunction "C_C") (pintype "passive"))
      (node (ref "D56") (pin "C") (pinfunction "C_C") (pintype "passive"))
      (node (ref "D57") (pin "C") (pinfunction "C_C") (pintype "passive"))
      (node (ref "D58") (pin "C") (pinfunction "C_C") (pintype "passive"))
      (node (ref "D59") (pin "C") (pinfunction "C_C") (pintype "passive"))
      (node (ref "D60") (pin "C") (pinfunction "C_C") (pintype "passive"))
      (node (ref "E34") (pin "10") (pinfunction "O_10") (pintype "output"))
    )
    (net (code "7") (name "C06") (class "Default")
      (node (ref "D61") (pin "C") (pinfunction "C_C") (pintype "passive"))
      (node (ref "D62") (pin "C") (pinfunction "C_C") (pintype "passive"))
      (node (ref "D63") (pin "C") (pinfunction "C_C") (pintype "passive"))
      (node (ref "D64") (pin "C") (pinfunction "C_C") (pintype "passive"))
      (node (ref "D65") (pin "C") (pinfunction "C_C") (pintype "passive"))
      (node (ref "D66") (pin "C") (pinfunction "C_C") (pintype "passive"))
      (node (ref "D67") (pin "C") (pinfunction "C_C") (pintype "passive"))
      (node (ref "D68") (pin "C") (pinfunction "C_C") (pintype "passive"))
      (node (ref "D69") (pin "C") (pinfunction "C_C") (pintype "passive"))
      (node (ref "D70") (pin "C") (pinfunction "C_C") (pintype "passive"))
      (node (ref "D71") (pin "C") (pinfunction "C_C") (pintype "passive"))
      (node (ref "D72") (pin "C") (pinfunction "C_C") (pintype "passive"))
      (node (ref "E34") (pin "8") (pinfunction "O_8") (pintype "output"))
    )
    (net (code "8") (name "C07") (class "Default")
      (node (ref "D73") (pin "C") (pinfunction "C_C") (pintype "passive"))
      (node (ref "D74") (pin "C") (pinfunction "C_C") (pintype "passive"))
      (node (ref "D75") (pin "C") (pinfunction "C_C") (pintype "passive"))
      (node (ref "D76") (pin "C") (pinfunction "C_C") (pintype "passive"))
      (node (ref "D77") (pin "C") (pinfunction "C_C") (pintype "passive"))
      (node (ref "D78") (pin "C") (pinfunction "C_C") (pintype "passive"))
      (node (ref "D79") (pin "C") (pinfunction "C_C") (pintype "passive"))
      (node (ref "D80") (pin "C") (pinfunction "C_C") (pintype "passive"))
      (node (ref "D81") (pin "C") (pinfunction "C_C") (pintype "passive"))
      (node (ref "D82") (pin "C") (pinfunction "C_C") (pintype "passive"))
      (node (ref "D83") (pin "C") (pinfunction "C_C") (pintype "passive"))
      (node (ref "D84") (pin "C") (pinfunction "C_C") (pintype "passive"))
      (node (ref "E28") (pin "6") (pinfunction "O_6") (pintype "output"))
    )
    (net (code "9") (name "C08") (class "Default")
      (node (ref "D85") (pin "C") (pinfunction "C_C") (pintype "passive"))
      (node (ref "D86") (pin "C") (pinfunction "C_C") (pintype "passive"))
      (node (ref "D87") (pin "C") (pinfunction "C_C") (pintype "passive"))
      (node (ref "D88") (pin "C") (pinfunction "C_C") (pintype "passive"))
      (node (ref "D89") (pin "C") (pinfunction "C_C") (pintype "passive"))
      (node (ref "D90") (pin "C") (pinfunction "C_C") (pintype "passive"))
      (node (ref "D91") (pin "C") (pinfunction "C_C") (pintype "passive"))
      (node (ref "D92") (pin "C") (pinfunction "C_C") (pintype "passive"))
      (node (ref "D93") (pin "C") (pinfunction "C_C") (pintype "passive"))
      (node (ref "D94") (pin "C") (pinfunction "C_C") (pintype "passive"))
      (node (ref "D95") (pin "C") (pinfunction "C_C") (pintype "passive"))
      (node (ref "D96") (pin "C") (pinfunction "C_C") (pintype "passive"))
      (node (ref "E28") (pin "4") (pinfunction "O_4") (pintype "output"))
    )
    (net (code "10") (name "C09") (class "Default")
      (node (ref "D100") (pin "C") (pinfunction "C_C") (pintype "passive"))
      (node (ref "D101") (pin "C") (pinfunction "C_C") (pintype "passive"))
      (node (ref "D102") (pin "C") (pinfunction "C_C") (pintype "passive"))
      (node (ref "D103") (pin "C") (pinfunction "C_C") (pintype "passive"))
      (node (ref "D104") (pin "C") (pinfunction "C_C") (pintype "passive"))
      (node (ref "D105") (pin "C") (pinfunction "C_C") (pintype "passive"))
      (node (ref "D106") (pin "C") (pinfunction "C_C") (pintype "passive"))
      (node (ref "D107") (pin "C") (pinfunction "C_C") (pintype "passive"))
      (node (ref "D108") (pin "C") (pinfunction "C_C") (pintype "passive"))
      (node (ref "D97") (pin "C") (pinfunction "C_C") (pintype "passive"))
      (node (ref "D98") (pin "C") (pinfunction "C_C") (pintype "passive"))
      (node (ref "D99") (pin "C") (pinfunction "C_C") (pintype "passive"))
      (node (ref "E28") (pin "2") (pinfunction "O_2") (pintype "output"))
    )
    (net (code "11") (name "C10") (class "Default")
      (node (ref "D109") (pin "C") (pinfunction "C_C") (pintype "passive"))
      (node (ref "D110") (pin "C") (pinfunction "C_C") (pintype "passive"))
      (node (ref "D111") (pin "C") (pinfunction "C_C") (pintype "passive"))
      (node (ref "D112") (pin "C") (pinfunction "C_C") (pintype "passive"))
      (node (ref "D113") (pin "C") (pinfunction "C_C") (pintype "passive"))
      (node (ref "D114") (pin "C") (pinfunction "C_C") (pintype "passive"))
      (node (ref "D115") (pin "C") (pinfunction "C_C") (pintype "passive"))
      (node (ref "D116") (pin "C") (pinfunction "C_C") (pintype "passive"))
      (node (ref "D117") (pin "C") (pinfunction "C_C") (pintype "passive"))
      (node (ref "D118") (pin "C") (pinfunction "C_C") (pintype "passive"))
      (node (ref "D119") (pin "C") (pinfunction "C_C") (pintype "passive"))
      (node (ref "D120") (pin "C") (pinfunction "C_C") (pintype "passive"))
      (node (ref "E28") (pin "12") (pinfunction "O_12") (pintype "output"))
    )
    (net (code "12") (name "C11") (class "Default")
      (node (ref "D121") (pin "C") (pinfunction "C_C") (pintype "passive"))
      (node (ref "D122") (pin "C") (pinfunction "C_C") (pintype "passive"))
      (node (ref "D123") (pin "C") (pinfunction "C_C") (pintype "passive"))
      (node (ref "D124") (pin "C") (pinfunction "C_C") (pintype "passive"))
      (node (ref "D125") (pin "C") (pinfunction "C_C") (pintype "passive"))
      (node (ref "D126") (pin "C") (pinfunction "C_C") (pintype "passive"))
      (node (ref "D127") (pin "C") (pinfunction "C_C") (pintype "passive"))
      (node (ref "D128") (pin "C") (pinfunction "C_C") (pintype "passive"))
      (node (ref "D129") (pin "C") (pinfunction "C_C") (pintype "passive"))
      (node (ref "D130") (pin "C") (pinfunction "C_C") (pintype "passive"))
      (node (ref "D131") (pin "C") (pinfunction "C_C") (pintype "passive"))
      (node (ref "D132") (pin "C") (pinfunction "C_C") (pintype "passive"))
      (node (ref "E28") (pin "10") (pinfunction "O_10") (pintype "output"))
    )
    (net (code "13") (name "C12") (class "Default")
      (node (ref "D133") (pin "C") (pinfunction "C_C") (pintype "passive"))
      (node (ref "D134") (pin "C") (pinfunction "C_C") (pintype "passive"))
      (node (ref "D135") (pin "C") (pinfunction "C_C") (pintype "passive"))
      (node (ref "D136") (pin "C") (pinfunction "C_C") (pintype "passive"))
      (node (ref "D137") (pin "C") (pinfunction "C_C") (pintype "passive"))
      (node (ref "D138") (pin "C") (pinfunction "C_C") (pintype "passive"))
      (node (ref "D139") (pin "C") (pinfunction "C_C") (pintype "passive"))
      (node (ref "D140") (pin "C") (pinfunction "C_C") (pintype "passive"))
      (node (ref "D141") (pin "C") (pinfunction "C_C") (pintype "passive"))
      (node (ref "D142") (pin "C") (pinfunction "C_C") (pintype "passive"))
      (node (ref "D143") (pin "C") (pinfunction "C_C") (pintype "passive"))
      (node (ref "D144") (pin "C") (pinfunction "C_C") (pintype "passive"))
      (node (ref "E28") (pin "8") (pinfunction "O_8") (pintype "output"))
    )
    (net (code "14") (name "C13") (class "Default")
      (node (ref "D145") (pin "C") (pinfunction "C_C") (pintype "passive"))
      (node (ref "D146") (pin "C") (pinfunction "C_C") (pintype "passive"))
      (node (ref "D147") (pin "C") (pinfunction "C_C") (pintype "passive"))
      (node (ref "D148") (pin "C") (pinfunction "C_C") (pintype "passive"))
      (node (ref "D149") (pin "C") (pinfunction "C_C") (pintype "passive"))
      (node (ref "D150") (pin "C") (pinfunction "C_C") (pintype "passive"))
      (node (ref "D151") (pin "C") (pinfunction "C_C") (pintype "passive"))
      (node (ref "D152") (pin "C") (pinfunction "C_C") (pintype "passive"))
      (node (ref "D153") (pin "C") (pinfunction "C_C") (pintype "passive"))
      (node (ref "D154") (pin "C") (pinfunction "C_C") (pintype "passive"))
      (node (ref "D155") (pin "C") (pinfunction "C_C") (pintype "passive"))
      (node (ref "D156") (pin "C") (pinfunction "C_C") (pintype "passive"))
      (node (ref "E24") (pin "2") (pinfunction "O_2") (pintype "output"))
    )
    (net (code "15") (name "C14") (class "Default")
      (node (ref "D157") (pin "C") (pinfunction "C_C") (pintype "passive"))
      (node (ref "D158") (pin "C") (pinfunction "C_C") (pintype "passive"))
      (node (ref "D159") (pin "C") (pinfunction "C_C") (pintype "passive"))
      (node (ref "D160") (pin "C") (pinfunction "C_C") (pintype "passive"))
      (node (ref "D161") (pin "C") (pinfunction "C_C") (pintype "passive"))
      (node (ref "D162") (pin "C") (pinfunction "C_C") (pintype "passive"))
      (node (ref "D163") (pin "C") (pinfunction "C_C") (pintype "passive"))
      (node (ref "D164") (pin "C") (pinfunction "C_C") (pintype "passive"))
      (node (ref "D165") (pin "C") (pinfunction "C_C") (pintype "passive"))
      (node (ref "D166") (pin "C") (pinfunction "C_C") (pintype "passive"))
      (node (ref "D167") (pin "C") (pinfunction "C_C") (pintype "passive"))
      (node (ref "D168") (pin "C") (pinfunction "C_C") (pintype "passive"))
      (node (ref "E24") (pin "12") (pinfunction "O_12") (pintype "output"))
    )
    (net (code "16") (name "C15") (class "Default")
      (node (ref "D169") (pin "C") (pinfunction "C_C") (pintype "passive"))
      (node (ref "D170") (pin "C") (pinfunction "C_C") (pintype "passive"))
      (node (ref "D171") (pin "C") (pinfunction "C_C") (pintype "passive"))
      (node (ref "D172") (pin "C") (pinfunction "C_C") (pintype "passive"))
      (node (ref "D173") (pin "C") (pinfunction "C_C") (pintype "passive"))
      (node (ref "D174") (pin "C") (pinfunction "C_C") (pintype "passive"))
      (node (ref "D175") (pin "C") (pinfunction "C_C") (pintype "passive"))
      (node (ref "D176") (pin "C") (pinfunction "C_C") (pintype "passive"))
      (node (ref "D177") (pin "C") (pinfunction "C_C") (pintype "passive"))
      (node (ref "D178") (pin "C") (pinfunction "C_C") (pintype "passive"))
      (node (ref "D179") (pin "C") (pinfunction "C_C") (pintype "passive"))
      (node (ref "D180") (pin "C") (pinfunction "C_C") (pintype "passive"))
      (node (ref "E24") (pin "10") (pinfunction "O_10") (pintype "output"))
    )
    (net (code "17") (name "C16") (class "Default")
      (node (ref "D181") (pin "C") (pinfunction "C_C") (pintype "passive"))
      (node (ref "D182") (pin "C") (pinfunction "C_C") (pintype "passive"))
      (node (ref "D183") (pin "C") (pinfunction "C_C") (pintype "passive"))
      (node (ref "D184") (pin "C") (pinfunction "C_C") (pintype "passive"))
      (node (ref "D185") (pin "C") (pinfunction "C_C") (pintype "passive"))
      (node (ref "D186") (pin "C") (pinfunction "C_C") (pintype "passive"))
      (node (ref "D187") (pin "C") (pinfunction "C_C") (pintype "passive"))
      (node (ref "D188") (pin "C") (pinfunction "C_C") (pintype "passive"))
      (node (ref "D189") (pin "C") (pinfunction "C_C") (pintype "passive"))
      (node (ref "D190") (pin "C") (pinfunction "C_C") (pintype "passive"))
      (node (ref "D191") (pin "C") (pinfunction "C_C") (pintype "passive"))
      (node (ref "D192") (pin "C") (pinfunction "C_C") (pintype "passive"))
      (node (ref "E24") (pin "8") (pinfunction "O_8") (pintype "output"))
    )
    (net (code "18") (name "C17") (class "Default")
      (node (ref "D193") (pin "C") (pinfunction "C_C") (pintype "passive"))
      (node (ref "D194") (pin "C") (pinfunction "C_C") (pintype "passive"))
      (node (ref "D195") (pin "C") (pinfunction "C_C") (pintype "passive"))
      (node (ref "D196") (pin "C") (pinfunction "C_C") (pintype "passive"))
      (node (ref "D197") (pin "C") (pinfunction "C_C") (pintype "passive"))
      (node (ref "D198") (pin "C") (pinfunction "C_C") (pintype "passive"))
      (node (ref "D199") (pin "C") (pinfunction "C_C") (pintype "passive"))
      (node (ref "D200") (pin "C") (pinfunction "C_C") (pintype "passive"))
      (node (ref "D201") (pin "C") (pinfunction "C_C") (pintype "passive"))
      (node (ref "D202") (pin "C") (pinfunction "C_C") (pintype "passive"))
      (node (ref "D203") (pin "C") (pinfunction "C_C") (pintype "passive"))
      (node (ref "D204") (pin "C") (pinfunction "C_C") (pintype "passive"))
      (node (ref "E10") (pin "2") (pinfunction "O_2") (pintype "output"))
    )
    (net (code "19") (name "C18") (class "Default")
      (node (ref "D205") (pin "C") (pinfunction "C_C") (pintype "passive"))
      (node (ref "D206") (pin "C") (pinfunction "C_C") (pintype "passive"))
      (node (ref "D207") (pin "C") (pinfunction "C_C") (pintype "passive"))
      (node (ref "D208") (pin "C") (pinfunction "C_C") (pintype "passive"))
      (node (ref "D209") (pin "C") (pinfunction "C_C") (pintype "passive"))
      (node (ref "D210") (pin "C") (pinfunction "C_C") (pintype "passive"))
      (node (ref "D211") (pin "C") (pinfunction "C_C") (pintype "passive"))
      (node (ref "D212") (pin "C") (pinfunction "C_C") (pintype "passive"))
      (node (ref "D213") (pin "C") (pinfunction "C_C") (pintype "passive"))
      (node (ref "D214") (pin "C") (pinfunction "C_C") (pintype "passive"))
      (node (ref "D215") (pin "C") (pinfunction "C_C") (pintype "passive"))
      (node (ref "D216") (pin "C") (pinfunction "C_C") (pintype "passive"))
      (node (ref "E10") (pin "12") (pinfunction "O_12") (pintype "output"))
    )
    (net (code "20") (name "C19") (class "Default")
      (node (ref "D217") (pin "C") (pinfunction "C_C") (pintype "passive"))
      (node (ref "D218") (pin "C") (pinfunction "C_C") (pintype "passive"))
      (node (ref "D219") (pin "C") (pinfunction "C_C") (pintype "passive"))
      (node (ref "D220") (pin "C") (pinfunction "C_C") (pintype "passive"))
      (node (ref "D221") (pin "C") (pinfunction "C_C") (pintype "passive"))
      (node (ref "D222") (pin "C") (pinfunction "C_C") (pintype "passive"))
      (node (ref "D223") (pin "C") (pinfunction "C_C") (pintype "passive"))
      (node (ref "D224") (pin "C") (pinfunction "C_C") (pintype "passive"))
      (node (ref "D225") (pin "C") (pinfunction "C_C") (pintype "passive"))
      (node (ref "D226") (pin "C") (pinfunction "C_C") (pintype "passive"))
      (node (ref "D227") (pin "C") (pinfunction "C_C") (pintype "passive"))
      (node (ref "D228") (pin "C") (pinfunction "C_C") (pintype "passive"))
      (node (ref "E10") (pin "10") (pinfunction "O_10") (pintype "output"))
    )
    (net (code "21") (name "C20") (class "Default")
      (node (ref "D229") (pin "C") (pinfunction "C_C") (pintype "passive"))
      (node (ref "D230") (pin "C") (pinfunction "C_C") (pintype "passive"))
      (node (ref "D231") (pin "C") (pinfunction "C_C") (pintype "passive"))
      (node (ref "D232") (pin "C") (pinfunction "C_C") (pintype "passive"))
      (node (ref "D233") (pin "C") (pinfunction "C_C") (pintype "passive"))
      (node (ref "D234") (pin "C") (pinfunction "C_C") (pintype "passive"))
      (node (ref "D235") (pin "C") (pinfunction "C_C") (pintype "passive"))
      (node (ref "D236") (pin "C") (pinfunction "C_C") (pintype "passive"))
      (node (ref "D237") (pin "C") (pinfunction "C_C") (pintype "passive"))
      (node (ref "D238") (pin "C") (pinfunction "C_C") (pintype "passive"))
      (node (ref "D239") (pin "C") (pinfunction "C_C") (pintype "passive"))
      (node (ref "D240") (pin "C") (pinfunction "C_C") (pintype "passive"))
      (node (ref "E10") (pin "8") (pinfunction "O_8") (pintype "output"))
    )
    (net (code "22") (name "C21") (class "Default")
      (node (ref "D241") (pin "C") (pinfunction "C_C") (pintype "passive"))
      (node (ref "D242") (pin "C") (pinfunction "C_C") (pintype "passive"))
      (node (ref "D243") (pin "C") (pinfunction "C_C") (pintype "passive"))
      (node (ref "D244") (pin "C") (pinfunction "C_C") (pintype "passive"))
      (node (ref "D245") (pin "C") (pinfunction "C_C") (pintype "passive"))
      (node (ref "D246") (pin "C") (pinfunction "C_C") (pintype "passive"))
      (node (ref "D247") (pin "C") (pinfunction "C_C") (pintype "passive"))
      (node (ref "D248") (pin "C") (pinfunction "C_C") (pintype "passive"))
      (node (ref "D249") (pin "C") (pinfunction "C_C") (pintype "passive"))
      (node (ref "D250") (pin "C") (pinfunction "C_C") (pintype "passive"))
      (node (ref "D251") (pin "C") (pinfunction "C_C") (pintype "passive"))
      (node (ref "D252") (pin "C") (pinfunction "C_C") (pintype "passive"))
      (node (ref "E8") (pin "6") (pinfunction "O_6") (pintype "output"))
    )
    (net (code "23") (name "C22") (class "Default")
      (node (ref "D253") (pin "C") (pinfunction "C_C") (pintype "passive"))
      (node (ref "D254") (pin "C") (pinfunction "C_C") (pintype "passive"))
      (node (ref "D255") (pin "C") (pinfunction "C_C") (pintype "passive"))
      (node (ref "D256") (pin "C") (pinfunction "C_C") (pintype "passive"))
      (node (ref "D257") (pin "C") (pinfunction "C_C") (pintype "passive"))
      (node (ref "D258") (pin "C") (pinfunction "C_C") (pintype "passive"))
      (node (ref "D259") (pin "C") (pinfunction "C_C") (pintype "passive"))
      (node (ref "D260") (pin "C") (pinfunction "C_C") (pintype "passive"))
      (node (ref "D261") (pin "C") (pinfunction "C_C") (pintype "passive"))
      (node (ref "D262") (pin "C") (pinfunction "C_C") (pintype "passive"))
      (node (ref "D263") (pin "C") (pinfunction "C_C") (pintype "passive"))
      (node (ref "D264") (pin "C") (pinfunction "C_C") (pintype "passive"))
      (node (ref "E8") (pin "4") (pinfunction "O_4") (pintype "output"))
    )
    (net (code "24") (name "C23") (class "Default")
      (node (ref "D265") (pin "C") (pinfunction "C_C") (pintype "passive"))
      (node (ref "D266") (pin "C") (pinfunction "C_C") (pintype "passive"))
      (node (ref "D267") (pin "C") (pinfunction "C_C") (pintype "passive"))
      (node (ref "D268") (pin "C") (pinfunction "C_C") (pintype "passive"))
      (node (ref "D269") (pin "C") (pinfunction "C_C") (pintype "passive"))
      (node (ref "D270") (pin "C") (pinfunction "C_C") (pintype "passive"))
      (node (ref "D271") (pin "C") (pinfunction "C_C") (pintype "passive"))
      (node (ref "D272") (pin "C") (pinfunction "C_C") (pintype "passive"))
      (node (ref "D273") (pin "C") (pinfunction "C_C") (pintype "passive"))
      (node (ref "D274") (pin "C") (pinfunction "C_C") (pintype "passive"))
      (node (ref "D275") (pin "C") (pinfunction "C_C") (pintype "passive"))
      (node (ref "D276") (pin "C") (pinfunction "C_C") (pintype "passive"))
      (node (ref "E8") (pin "2") (pinfunction "O_2") (pintype "output"))
    )
    (net (code "25") (name "C24") (class "Default")
      (node (ref "D277") (pin "C") (pinfunction "C_C") (pintype "passive"))
      (node (ref "D278") (pin "C") (pinfunction "C_C") (pintype "passive"))
      (node (ref "D279") (pin "C") (pinfunction "C_C") (pintype "passive"))
      (node (ref "D280") (pin "C") (pinfunction "C_C") (pintype "passive"))
      (node (ref "D281") (pin "C") (pinfunction "C_C") (pintype "passive"))
      (node (ref "D282") (pin "C") (pinfunction "C_C") (pintype "passive"))
      (node (ref "D283") (pin "C") (pinfunction "C_C") (pintype "passive"))
      (node (ref "D284") (pin "C") (pinfunction "C_C") (pintype "passive"))
      (node (ref "D285") (pin "C") (pinfunction "C_C") (pintype "passive"))
      (node (ref "D286") (pin "C") (pinfunction "C_C") (pintype "passive"))
      (node (ref "D287") (pin "C") (pinfunction "C_C") (pintype "passive"))
      (node (ref "D288") (pin "C") (pinfunction "C_C") (pintype "passive"))
      (node (ref "E8") (pin "12") (pinfunction "O_12") (pintype "output"))
    )
    (net (code "26") (name "C25") (class "Default")
      (node (ref "D289") (pin "C") (pinfunction "C_C") (pintype "passive"))
      (node (ref "D290") (pin "C") (pinfunction "C_C") (pintype "passive"))
      (node (ref "D291") (pin "C") (pinfunction "C_C") (pintype "passive"))
      (node (ref "D292") (pin "C") (pinfunction "C_C") (pintype "passive"))
      (node (ref "D293") (pin "C") (pinfunction "C_C") (pintype "passive"))
      (node (ref "D294") (pin "C") (pinfunction "C_C") (pintype "passive"))
      (node (ref "D295") (pin "C") (pinfunction "C_C") (pintype "passive"))
      (node (ref "D296") (pin "C") (pinfunction "C_C") (pintype "passive"))
      (node (ref "D297") (pin "C") (pinfunction "C_C") (pintype "passive"))
      (node (ref "D298") (pin "C") (pinfunction "C_C") (pintype "passive"))
      (node (ref "D299") (pin "C") (pinfunction "C_C") (pintype "passive"))
      (node (ref "D300") (pin "C") (pinfunction "C_C") (pintype "passive"))
      (node (ref "E8") (pin "10") (pinfunction "O_10") (pintype "output"))
    )
    (net (code "27") (name "C26") (class "Default")
      (node (ref "D301") (pin "C") (pinfunction "C_C") (pintype "passive"))
      (node (ref "D302") (pin "C") (pinfunction "C_C") (pintype "passive"))
      (node (ref "D303") (pin "C") (pinfunction "C_C") (pintype "passive"))
      (node (ref "D304") (pin "C") (pinfunction "C_C") (pintype "passive"))
      (node (ref "D305") (pin "C") (pinfunction "C_C") (pintype "passive"))
      (node (ref "D306") (pin "C") (pinfunction "C_C") (pintype "passive"))
      (node (ref "D307") (pin "C") (pinfunction "C_C") (pintype "passive"))
      (node (ref "D308") (pin "C") (pinfunction "C_C") (pintype "passive"))
      (node (ref "D309") (pin "C") (pinfunction "C_C") (pintype "passive"))
      (node (ref "D310") (pin "C") (pinfunction "C_C") (pintype "passive"))
      (node (ref "D311") (pin "C") (pinfunction "C_C") (pintype "passive"))
      (node (ref "D312") (pin "C") (pinfunction "C_C") (pintype "passive"))
      (node (ref "E8") (pin "8") (pinfunction "O_8") (pintype "output"))
    )
    (net (code "28") (name "C27") (class "Default")
      (node (ref "D313") (pin "C") (pinfunction "C_C") (pintype "passive"))
      (node (ref "D314") (pin "C") (pinfunction "C_C") (pintype "passive"))
      (node (ref "D315") (pin "C") (pinfunction "C_C") (pintype "passive"))
      (node (ref "D316") (pin "C") (pinfunction "C_C") (pintype "passive"))
      (node (ref "D317") (pin "C") (pinfunction "C_C") (pintype "passive"))
      (node (ref "D318") (pin "C") (pinfunction "C_C") (pintype "passive"))
      (node (ref "D319") (pin "C") (pinfunction "C_C") (pintype "passive"))
      (node (ref "D320") (pin "C") (pinfunction "C_C") (pintype "passive"))
      (node (ref "D321") (pin "C") (pinfunction "C_C") (pintype "passive"))
      (node (ref "D322") (pin "C") (pinfunction "C_C") (pintype "passive"))
      (node (ref "D323") (pin "C") (pinfunction "C_C") (pintype "passive"))
      (node (ref "D324") (pin "C") (pinfunction "C_C") (pintype "passive"))
      (node (ref "E3") (pin "6") (pinfunction "O_6") (pintype "output"))
    )
    (net (code "29") (name "C28") (class "Default")
      (node (ref "D325") (pin "C") (pinfunction "C_C") (pintype "passive"))
      (node (ref "D326") (pin "C") (pinfunction "C_C") (pintype "passive"))
      (node (ref "D327") (pin "C") (pinfunction "C_C") (pintype "passive"))
      (node (ref "D328") (pin "C") (pinfunction "C_C") (pintype "passive"))
      (node (ref "D329") (pin "C") (pinfunction "C_C") (pintype "passive"))
      (node (ref "D330") (pin "C") (pinfunction "C_C") (pintype "passive"))
      (node (ref "D331") (pin "C") (pinfunction "C_C") (pintype "passive"))
      (node (ref "D332") (pin "C") (pinfunction "C_C") (pintype "passive"))
      (node (ref "D333") (pin "C") (pinfunction "C_C") (pintype "passive"))
      (node (ref "D334") (pin "C") (pinfunction "C_C") (pintype "passive"))
      (node (ref "D335") (pin "C") (pinfunction "C_C") (pintype "passive"))
      (node (ref "D336") (pin "C") (pinfunction "C_C") (pintype "passive"))
      (node (ref "E3") (pin "4") (pinfunction "O_4") (pintype "output"))
    )
    (net (code "30") (name "C29") (class "Default")
      (node (ref "D337") (pin "C") (pinfunction "C_C") (pintype "passive"))
      (node (ref "D338") (pin "C") (pinfunction "C_C") (pintype "passive"))
      (node (ref "D339") (pin "C") (pinfunction "C_C") (pintype "passive"))
      (node (ref "D340") (pin "C") (pinfunction "C_C") (pintype "passive"))
      (node (ref "D341") (pin "C") (pinfunction "C_C") (pintype "passive"))
      (node (ref "D342") (pin "C") (pinfunction "C_C") (pintype "passive"))
      (node (ref "D343") (pin "C") (pinfunction "C_C") (pintype "passive"))
      (node (ref "D344") (pin "C") (pinfunction "C_C") (pintype "passive"))
      (node (ref "D345") (pin "C") (pinfunction "C_C") (pintype "passive"))
      (node (ref "D346") (pin "C") (pinfunction "C_C") (pintype "passive"))
      (node (ref "D347") (pin "C") (pinfunction "C_C") (pintype "passive"))
      (node (ref "D348") (pin "C") (pinfunction "C_C") (pintype "passive"))
      (node (ref "E3") (pin "2") (pinfunction "O_2") (pintype "output"))
    )
    (net (code "31") (name "C30") (class "Default")
      (node (ref "D349") (pin "C") (pinfunction "C_C") (pintype "passive"))
      (node (ref "D350") (pin "C") (pinfunction "C_C") (pintype "passive"))
      (node (ref "D351") (pin "C") (pinfunction "C_C") (pintype "passive"))
      (node (ref "D352") (pin "C") (pinfunction "C_C") (pintype "passive"))
      (node (ref "D353") (pin "C") (pinfunction "C_C") (pintype "passive"))
      (node (ref "D354") (pin "C") (pinfunction "C_C") (pintype "passive"))
      (node (ref "D355") (pin "C") (pinfunction "C_C") (pintype "passive"))
      (node (ref "D356") (pin "C") (pinfunction "C_C") (pintype "passive"))
      (node (ref "D357") (pin "C") (pinfunction "C_C") (pintype "passive"))
      (node (ref "D358") (pin "C") (pinfunction "C_C") (pintype "passive"))
      (node (ref "D359") (pin "C") (pinfunction "C_C") (pintype "passive"))
      (node (ref "D360") (pin "C") (pinfunction "C_C") (pintype "passive"))
      (node (ref "E3") (pin "12") (pinfunction "O_12") (pintype "output"))
    )
    (net (code "32") (name "C31") (class "Default")
      (node (ref "D361") (pin "C") (pinfunction "C_C") (pintype "passive"))
      (node (ref "D362") (pin "C") (pinfunction "C_C") (pintype "passive"))
      (node (ref "D363") (pin "C") (pinfunction "C_C") (pintype "passive"))
      (node (ref "D364") (pin "C") (pinfunction "C_C") (pintype "passive"))
      (node (ref "D365") (pin "C") (pinfunction "C_C") (pintype "passive"))
      (node (ref "D366") (pin "C") (pinfunction "C_C") (pintype "passive"))
      (node (ref "D367") (pin "C") (pinfunction "C_C") (pintype "passive"))
      (node (ref "D368") (pin "C") (pinfunction "C_C") (pintype "passive"))
      (node (ref "D369") (pin "C") (pinfunction "C_C") (pintype "passive"))
      (node (ref "D370") (pin "C") (pinfunction "C_C") (pintype "passive"))
      (node (ref "D371") (pin "C") (pinfunction "C_C") (pintype "passive"))
      (node (ref "D372") (pin "C") (pinfunction "C_C") (pintype "passive"))
      (node (ref "E3") (pin "10") (pinfunction "O_10") (pintype "output"))
    )
    (net (code "33") (name "C32") (class "Default")
      (node (ref "D373") (pin "C") (pinfunction "C_C") (pintype "passive"))
      (node (ref "D374") (pin "C") (pinfunction "C_C") (pintype "passive"))
      (node (ref "D375") (pin "C") (pinfunction "C_C") (pintype "passive"))
      (node (ref "D376") (pin "C") (pinfunction "C_C") (pintype "passive"))
      (node (ref "D377") (pin "C") (pinfunction "C_C") (pintype "passive"))
      (node (ref "D378") (pin "C") (pinfunction "C_C") (pintype "passive"))
      (node (ref "D379") (pin "C") (pinfunction "C_C") (pintype "passive"))
      (node (ref "D380") (pin "C") (pinfunction "C_C") (pintype "passive"))
      (node (ref "D381") (pin "C") (pinfunction "C_C") (pintype "passive"))
      (node (ref "D382") (pin "C") (pinfunction "C_C") (pintype "passive"))
      (node (ref "D383") (pin "C") (pinfunction "C_C") (pintype "passive"))
      (node (ref "D384") (pin "C") (pinfunction "C_C") (pintype "passive"))
      (node (ref "E3") (pin "8") (pinfunction "O_8") (pintype "output"))
    )
    (net (code "34") (name "DATA_ENAB") (class "Default")
      (node (ref "E14") (pin "12") (pinfunction "I1_12") (pintype "input"))
      (node (ref "E14") (pin "3") (pinfunction "I1_3") (pintype "input"))
      (node (ref "E14") (pin "6") (pinfunction "I1_6") (pintype "input"))
      (node (ref "E14") (pin "9") (pinfunction "I1_9") (pintype "input"))
      (node (ref "E4") (pin "12") (pinfunction "I1_12") (pintype "input"))
      (node (ref "E4") (pin "3") (pinfunction "I1_3") (pintype "input"))
      (node (ref "E4") (pin "6") (pinfunction "I1_6") (pintype "input"))
      (node (ref "E4") (pin "9") (pinfunction "I1_9") (pintype "input"))
      (node (ref "IC7") (pin "12") (pinfunction "I1_12") (pintype "input"))
      (node (ref "IC7") (pin "3") (pinfunction "I1_3") (pintype "input"))
      (node (ref "IC7") (pin "6") (pinfunction "I1_6") (pintype "input"))
      (node (ref "IC7") (pin "9") (pinfunction "I1_9") (pintype "input"))
    )
    (net (code "35") (name "GND") (class "Default")
      (node (ref "E27") (pin "6") (pinfunction "I0_6") (pintype "input"))
      (node (ref "E27") (pin "7") (pinfunction "I1_7") (pintype "input"))
      (node (ref "U$2") (pin "AC2") (pinfunction "1_AC2") (pintype "bidirectional"))
      (node (ref "U$2") (pin "AF1") (pinfunction "1_AF1") (pintype "bidirectional"))
      (node (ref "U$2") (pin "AF2") (pinfunction "1_AF2") (pintype "bidirectional"))
      (node (ref "U$2") (pin "AN1") (pinfunction "1_AN1") (pintype "bidirectional"))
      (node (ref "U$2") (pin "AN2") (pinfunction "1_AN2") (pintype "bidirectional"))
      (node (ref "U$2") (pin "AT1") (pinfunction "1_AT1") (pintype "bidirectional"))
      (node (ref "U$2") (pin "AT2") (pinfunction "1_AT2") (pintype "bidirectional"))
      (node (ref "U$2") (pin "BC1") (pinfunction "1_BC1") (pintype "bidirectional"))
      (node (ref "U$2") (pin "BC2") (pinfunction "1_BC2") (pintype "bidirectional"))
      (node (ref "U$2") (pin "BF1") (pinfunction "1_BF1") (pintype "bidirectional"))
      (node (ref "U$2") (pin "BF2") (pinfunction "1_BF2") (pintype "bidirectional"))
      (node (ref "U$2") (pin "BN1") (pinfunction "1_BN1") (pintype "bidirectional"))
      (node (ref "U$2") (pin "BN2") (pinfunction "1_BN2") (pintype "bidirectional"))
      (node (ref "U$2") (pin "BT1") (pinfunction "1_BT1") (pintype "bidirectional"))
      (node (ref "U$2") (pin "CC1") (pinfunction "1_CC1") (pintype "bidirectional"))
      (node (ref "U$2") (pin "CC2") (pinfunction "1_CC2") (pintype "bidirectional"))
      (node (ref "U$2") (pin "CF2") (pinfunction "1_CF2") (pintype "bidirectional"))
      (node (ref "U$2") (pin "CN1") (pinfunction "1_CN1") (pintype "bidirectional"))
      (node (ref "U$2") (pin "CN2") (pinfunction "1_CN2") (pintype "bidirectional"))
      (node (ref "U$2") (pin "CT1") (pinfunction "1_CT1") (pintype "bidirectional"))
      (node (ref "U$2") (pin "CT2") (pinfunction "1_CT2") (pintype "bidirectional"))
      (node (ref "U$2") (pin "DC1") (pinfunction "1_DC1") (pintype "bidirectional"))
      (node (ref "U$2") (pin "DC2") (pinfunction "1_DC2") (pintype "bidirectional"))
      (node (ref "U$2") (pin "DF1") (pinfunction "1_DF1") (pintype "bidirectional"))
      (node (ref "U$2") (pin "DF2") (pinfunction "1_DF2") (pintype "bidirectional"))
      (node (ref "U$2") (pin "DN1") (pinfunction "1_DN1") (pintype "bidirectional"))
      (node (ref "U$2") (pin "DN2") (pinfunction "1_DN2") (pintype "bidirectional"))
      (node (ref "U$2") (pin "DT1") (pinfunction "1_DT1") (pintype "bidirectional"))
      (node (ref "U$2") (pin "DT2") (pinfunction "1_DT2") (pintype "bidirectional"))
    )
    (net (code "36") (name "INITIALIZE") (class "Default")
      (node (ref "U$2") (pin "CR1") (pinfunction "1_CR1") (pintype "bidirectional"))
    )
    (net (code "37") (name "LAST_WORD") (class "Default")
      (node (ref "E3") (pin "9") (pinfunction "I_9") (pintype "input"))
      (node (ref "E6") (pin "13") (pinfunction "QH_13") (pintype "output"))
    )
    (net (code "38") (name "Net-(E1A-I0)") (class "Default")
      (node (ref "D111") (pin "A") (pinfunction "A_A") (pintype "passive"))
      (node (ref "D123") (pin "A") (pinfunction "A_A") (pintype "passive"))
      (node (ref "D135") (pin "A") (pinfunction "A_A") (pintype "passive"))
      (node (ref "D147") (pin "A") (pinfunction "A_A") (pintype "passive"))
      (node (ref "D15") (pin "A") (pinfunction "A_A") (pintype "passive"))
      (node (ref "D159") (pin "A") (pinfunction "A_A") (pintype "passive"))
      (node (ref "D171") (pin "A") (pinfunction "A_A") (pintype "passive"))
      (node (ref "D183") (pin "A") (pinfunction "A_A") (pintype "passive"))
      (node (ref "D195") (pin "A") (pinfunction "A_A") (pintype "passive"))
      (node (ref "D207") (pin "A") (pinfunction "A_A") (pintype "passive"))
      (node (ref "D219") (pin "A") (pinfunction "A_A") (pintype "passive"))
      (node (ref "D231") (pin "A") (pinfunction "A_A") (pintype "passive"))
      (node (ref "D243") (pin "A") (pinfunction "A_A") (pintype "passive"))
      (node (ref "D255") (pin "A") (pinfunction "A_A") (pintype "passive"))
      (node (ref "D267") (pin "A") (pinfunction "A_A") (pintype "passive"))
      (node (ref "D27") (pin "A") (pinfunction "A_A") (pintype "passive"))
      (node (ref "D279") (pin "A") (pinfunction "A_A") (pintype "passive"))
      (node (ref "D291") (pin "A") (pinfunction "A_A") (pintype "passive"))
      (node (ref "D3") (pin "A") (pinfunction "A_A") (pintype "passive"))
      (node (ref "D303") (pin "A") (pinfunction "A_A") (pintype "passive"))
      (node (ref "D315") (pin "A") (pinfunction "A_A") (pintype "passive"))
      (node (ref "D327") (pin "A") (pinfunction "A_A") (pintype "passive"))
      (node (ref "D339") (pin "A") (pinfunction "A_A") (pintype "passive"))
      (node (ref "D351") (pin "A") (pinfunction "A_A") (pintype "passive"))
      (node (ref "D363") (pin "A") (pinfunction "A_A") (pintype "passive"))
      (node (ref "D375") (pin "A") (pinfunction "A_A") (pintype "passive"))
      (node (ref "D39") (pin "A") (pinfunction "A_A") (pintype "passive"))
      (node (ref "D51") (pin "A") (pinfunction "A_A") (pintype "passive"))
      (node (ref "D63") (pin "A") (pinfunction "A_A") (pintype "passive"))
      (node (ref "D75") (pin "A") (pinfunction "A_A") (pintype "passive"))
      (node (ref "D87") (pin "A") (pinfunction "A_A") (pintype "passive"))
      (node (ref "D99") (pin "A") (pinfunction "A_A") (pintype "passive"))
      (node (ref "E1") (pin "4") (pinfunction "I0_4") (pintype "input"))
      (node (ref "E1") (pin "5") (pinfunction "I1_5") (pintype "input"))
    )
    (net (code "39") (name "Net-(E1A-O)") (class "Default")
      (node (ref "E1") (pin "3") (pinfunction "O_3") (pintype "output"))
      (node (ref "E4") (pin "5") (pinfunction "I0_5") (pintype "input"))
    )
    (net (code "40") (name "Net-(E1B-I0)") (class "Default")
      (node (ref "D100") (pin "A") (pinfunction "A_A") (pintype "passive"))
      (node (ref "D112") (pin "A") (pinfunction "A_A") (pintype "passive"))
      (node (ref "D124") (pin "A") (pinfunction "A_A") (pintype "passive"))
      (node (ref "D136") (pin "A") (pinfunction "A_A") (pintype "passive"))
      (node (ref "D148") (pin "A") (pinfunction "A_A") (pintype "passive"))
      (node (ref "D16") (pin "A") (pinfunction "A_A") (pintype "passive"))
      (node (ref "D160") (pin "A") (pinfunction "A_A") (pintype "passive"))
      (node (ref "D172") (pin "A") (pinfunction "A_A") (pintype "passive"))
      (node (ref "D184") (pin "A") (pinfunction "A_A") (pintype "passive"))
      (node (ref "D196") (pin "A") (pinfunction "A_A") (pintype "passive"))
      (node (ref "D208") (pin "A") (pinfunction "A_A") (pintype "passive"))
      (node (ref "D220") (pin "A") (pinfunction "A_A") (pintype "passive"))
      (node (ref "D232") (pin "A") (pinfunction "A_A") (pintype "passive"))
      (node (ref "D244") (pin "A") (pinfunction "A_A") (pintype "passive"))
      (node (ref "D256") (pin "A") (pinfunction "A_A") (pintype "passive"))
      (node (ref "D268") (pin "A") (pinfunction "A_A") (pintype "passive"))
      (node (ref "D28") (pin "A") (pinfunction "A_A") (pintype "passive"))
      (node (ref "D280") (pin "A") (pinfunction "A_A") (pintype "passive"))
      (node (ref "D292") (pin "A") (pinfunction "A_A") (pintype "passive"))
      (node (ref "D304") (pin "A") (pinfunction "A_A") (pintype "passive"))
      (node (ref "D316") (pin "A") (pinfunction "A_A") (pintype "passive"))
      (node (ref "D328") (pin "A") (pinfunction "A_A") (pintype "passive"))
      (node (ref "D340") (pin "A") (pinfunction "A_A") (pintype "passive"))
      (node (ref "D352") (pin "A") (pinfunction "A_A") (pintype "passive"))
      (node (ref "D364") (pin "A") (pinfunction "A_A") (pintype "passive"))
      (node (ref "D376") (pin "A") (pinfunction "A_A") (pintype "passive"))
      (node (ref "D4") (pin "A") (pinfunction "A_A") (pintype "passive"))
      (node (ref "D40") (pin "A") (pinfunction "A_A") (pintype "passive"))
      (node (ref "D52") (pin "A") (pinfunction "A_A") (pintype "passive"))
      (node (ref "D64") (pin "A") (pinfunction "A_A") (pintype "passive"))
      (node (ref "D76") (pin "A") (pinfunction "A_A") (pintype "passive"))
      (node (ref "D88") (pin "A") (pinfunction "A_A") (pintype "passive"))
      (node (ref "E1") (pin "6") (pinfunction "I0_6") (pintype "input"))
      (node (ref "E1") (pin "7") (pinfunction "I1_7") (pintype "input"))
    )
    (net (code "41") (name "Net-(E1B-O)") (class "Default")
      (node (ref "E1") (pin "2") (pinfunction "O_2") (pintype "output"))
      (node (ref "E4") (pin "2") (pinfunction "I0_2") (pintype "input"))
    )
    (net (code "42") (name "Net-(E1C-I0)") (class "Default")
      (node (ref "D110") (pin "A") (pinfunction "A_A") (pintype "passive"))
      (node (ref "D122") (pin "A") (pinfunction "A_A") (pintype "passive"))
      (node (ref "D134") (pin "A") (pinfunction "A_A") (pintype "passive"))
      (node (ref "D14") (pin "A") (pinfunction "A_A") (pintype "passive"))
      (node (ref "D146") (pin "A") (pinfunction "A_A") (pintype "passive"))
      (node (ref "D158") (pin "A") (pinfunction "A_A") (pintype "passive"))
      (node (ref "D170") (pin "A") (pinfunction "A_A") (pintype "passive"))
      (node (ref "D182") (pin "A") (pinfunction "A_A") (pintype "passive"))
      (node (ref "D194") (pin "A") (pinfunction "A_A") (pintype "passive"))
      (node (ref "D2") (pin "A") (pinfunction "A_A") (pintype "passive"))
      (node (ref "D206") (pin "A") (pinfunction "A_A") (pintype "passive"))
      (node (ref "D218") (pin "A") (pinfunction "A_A") (pintype "passive"))
      (node (ref "D230") (pin "A") (pinfunction "A_A") (pintype "passive"))
      (node (ref "D242") (pin "A") (pinfunction "A_A") (pintype "passive"))
      (node (ref "D254") (pin "A") (pinfunction "A_A") (pintype "passive"))
      (node (ref "D26") (pin "A") (pinfunction "A_A") (pintype "passive"))
      (node (ref "D266") (pin "A") (pinfunction "A_A") (pintype "passive"))
      (node (ref "D278") (pin "A") (pinfunction "A_A") (pintype "passive"))
      (node (ref "D290") (pin "A") (pinfunction "A_A") (pintype "passive"))
      (node (ref "D302") (pin "A") (pinfunction "A_A") (pintype "passive"))
      (node (ref "D314") (pin "A") (pinfunction "A_A") (pintype "passive"))
      (node (ref "D326") (pin "A") (pinfunction "A_A") (pintype "passive"))
      (node (ref "D338") (pin "A") (pinfunction "A_A") (pintype "passive"))
      (node (ref "D350") (pin "A") (pinfunction "A_A") (pintype "passive"))
      (node (ref "D362") (pin "A") (pinfunction "A_A") (pintype "passive"))
      (node (ref "D374") (pin "A") (pinfunction "A_A") (pintype "passive"))
      (node (ref "D38") (pin "A") (pinfunction "A_A") (pintype "passive"))
      (node (ref "D50") (pin "A") (pinfunction "A_A") (pintype "passive"))
      (node (ref "D62") (pin "A") (pinfunction "A_A") (pintype "passive"))
      (node (ref "D74") (pin "A") (pinfunction "A_A") (pintype "passive"))
      (node (ref "D86") (pin "A") (pinfunction "A_A") (pintype "passive"))
      (node (ref "D98") (pin "A") (pinfunction "A_A") (pintype "passive"))
      (node (ref "E1") (pin "10") (pinfunction "I1_10") (pintype "input"))
      (node (ref "E1") (pin "9") (pinfunction "I0_9") (pintype "input"))
    )
    (net (code "43") (name "Net-(E1C-O)") (class "Default")
      (node (ref "E1") (pin "14") (pinfunction "O_14") (pintype "output"))
      (node (ref "E4") (pin "11") (pinfunction "I0_11") (pintype "input"))
    )
    (net (code "44") (name "Net-(E1D-I0)") (class "Default")
      (node (ref "D1") (pin "A") (pinfunction "A_A") (pintype "passive"))
      (node (ref "D109") (pin "A") (pinfunction "A_A") (pintype "passive"))
      (node (ref "D121") (pin "A") (pinfunction "A_A") (pintype "passive"))
      (node (ref "D13") (pin "A") (pinfunction "A_A") (pintype "passive"))
      (node (ref "D133") (pin "A") (pinfunction "A_A") (pintype "passive"))
      (node (ref "D145") (pin "A") (pinfunction "A_A") (pintype "passive"))
      (node (ref "D157") (pin "A") (pinfunction "A_A") (pintype "passive"))
      (node (ref "D169") (pin "A") (pinfunction "A_A") (pintype "passive"))
      (node (ref "D181") (pin "A") (pinfunction "A_A") (pintype "passive"))
      (node (ref "D193") (pin "A") (pinfunction "A_A") (pintype "passive"))
      (node (ref "D205") (pin "A") (pinfunction "A_A") (pintype "passive"))
      (node (ref "D217") (pin "A") (pinfunction "A_A") (pintype "passive"))
      (node (ref "D229") (pin "A") (pinfunction "A_A") (pintype "passive"))
      (node (ref "D241") (pin "A") (pinfunction "A_A") (pintype "passive"))
      (node (ref "D25") (pin "A") (pinfunction "A_A") (pintype "passive"))
      (node (ref "D253") (pin "A") (pinfunction "A_A") (pintype "passive"))
      (node (ref "D265") (pin "A") (pinfunction "A_A") (pintype "passive"))
      (node (ref "D277") (pin "A") (pinfunction "A_A") (pintype "passive"))
      (node (ref "D289") (pin "A") (pinfunction "A_A") (pintype "passive"))
      (node (ref "D301") (pin "A") (pinfunction "A_A") (pintype "passive"))
      (node (ref "D313") (pin "A") (pinfunction "A_A") (pintype "passive"))
      (node (ref "D325") (pin "A") (pinfunction "A_A") (pintype "passive"))
      (node (ref "D337") (pin "A") (pinfunction "A_A") (pintype "passive"))
      (node (ref "D349") (pin "A") (pinfunction "A_A") (pintype "passive"))
      (node (ref "D361") (pin "A") (pinfunction "A_A") (pintype "passive"))
      (node (ref "D37") (pin "A") (pinfunction "A_A") (pintype "passive"))
      (node (ref "D373") (pin "A") (pinfunction "A_A") (pintype "passive"))
      (node (ref "D49") (pin "A") (pinfunction "A_A") (pintype "passive"))
      (node (ref "D61") (pin "A") (pinfunction "A_A") (pintype "passive"))
      (node (ref "D73") (pin "A") (pinfunction "A_A") (pintype "passive"))
      (node (ref "D85") (pin "A") (pinfunction "A_A") (pintype "passive"))
      (node (ref "D97") (pin "A") (pinfunction "A_A") (pintype "passive"))
      (node (ref "E1") (pin "11") (pinfunction "I0_11") (pintype "input"))
      (node (ref "E1") (pin "12") (pinfunction "I1_12") (pintype "input"))
    )
    (net (code "45") (name "Net-(E1D-O)") (class "Default")
      (node (ref "E1") (pin "13") (pinfunction "O_13") (pintype "output"))
      (node (ref "E4") (pin "8") (pinfunction "I0_8") (pintype "input"))
    )
    (net (code "46") (name "Net-(E3A-I)") (class "Default")
      (node (ref "E3") (pin "1") (pinfunction "I_1") (pintype "input"))
      (node (ref "E6") (pin "10") (pinfunction "QE_10") (pintype "output"))
    )
    (net (code "47") (name "Net-(E3B-I)") (class "Default")
      (node (ref "E3") (pin "3") (pinfunction "I_3") (pintype "input"))
      (node (ref "E6") (pin "6") (pinfunction "QD_6") (pintype "output"))
    )
    (net (code "48") (name "Net-(E3C-I)") (class "Default")
      (node (ref "E3") (pin "5") (pinfunction "I_5") (pintype "input"))
      (node (ref "E6") (pin "5") (pinfunction "QC_5") (pintype "output"))
    )
    (net (code "49") (name "Net-(E3E-I)") (class "Default")
      (node (ref "E3") (pin "11") (pinfunction "I_11") (pintype "input"))
      (node (ref "E6") (pin "12") (pinfunction "QG_12") (pintype "output"))
    )
    (net (code "50") (name "Net-(E3F-I)") (class "Default")
      (node (ref "E3") (pin "13") (pinfunction "I_13") (pintype "input"))
      (node (ref "E6") (pin "11") (pinfunction "QF_11") (pintype "output"))
    )
    (net (code "51") (name "Net-(E6A-A)") (class "Default")
      (node (ref "E6") (pin "1") (pinfunction "A_1") (pintype "input"))
      (node (ref "E6") (pin "2") (pinfunction "B_2") (pintype "input"))
      (node (ref "E8") (pin "13") (pinfunction "I_13") (pintype "input"))
      (node (ref "E9") (pin "13") (pinfunction "QH_13") (pintype "output"))
    )
    (net (code "52") (name "Net-(E6A-QA)") (class "Default")
      (node (ref "E6") (pin "3") (pinfunction "QA_3") (pintype "output"))
      (node (ref "E8") (pin "11") (pinfunction "I_11") (pintype "input"))
    )
    (net (code "53") (name "Net-(E6A-QB)") (class "Default")
      (node (ref "E6") (pin "4") (pinfunction "QB_4") (pintype "output"))
      (node (ref "E8") (pin "9") (pinfunction "I_9") (pintype "input"))
    )
    (net (code "54") (name "Net-(E8A-I)") (class "Default")
      (node (ref "E8") (pin "1") (pinfunction "I_1") (pintype "input"))
      (node (ref "E9") (pin "12") (pinfunction "QG_12") (pintype "output"))
    )
    (net (code "55") (name "Net-(E8B-I)") (class "Default")
      (node (ref "E8") (pin "3") (pinfunction "I_3") (pintype "input"))
      (node (ref "E9") (pin "11") (pinfunction "QF_11") (pintype "output"))
    )
    (net (code "56") (name "Net-(E8C-I)") (class "Default")
      (node (ref "E8") (pin "5") (pinfunction "I_5") (pintype "input"))
      (node (ref "E9") (pin "10") (pinfunction "QE_10") (pintype "output"))
    )
    (net (code "57") (name "Net-(E10A-I)") (class "Default")
      (node (ref "E10") (pin "1") (pinfunction "I_1") (pintype "input"))
      (node (ref "E9") (pin "3") (pinfunction "QA_3") (pintype "output"))
    )
    (net (code "58") (name "Net-(E10D-I)") (class "Default")
      (node (ref "E10") (pin "9") (pinfunction "I_9") (pintype "input"))
      (node (ref "E9") (pin "6") (pinfunction "QD_6") (pintype "output"))
    )
    (net (code "59") (name "Net-(E10E-I)") (class "Default")
      (node (ref "E10") (pin "11") (pinfunction "I_11") (pintype "input"))
      (node (ref "E9") (pin "5") (pinfunction "QC_5") (pintype "output"))
    )
    (net (code "60") (name "Net-(E10F-I)") (class "Default")
      (node (ref "E10") (pin "13") (pinfunction "I_13") (pintype "input"))
      (node (ref "E9") (pin "4") (pinfunction "QB_4") (pintype "output"))
    )
    (net (code "61") (name "Net-(E14A-I0)") (class "Default")
      (node (ref "E14") (pin "2") (pinfunction "I0_2") (pintype "input"))
      (node (ref "E17") (pin "14") (pinfunction "O_14") (pintype "output"))
    )
    (net (code "62") (name "Net-(E14B-I0)") (class "Default")
      (node (ref "E14") (pin "5") (pinfunction "I0_5") (pintype "input"))
      (node (ref "E17") (pin "13") (pinfunction "O_13") (pintype "output"))
    )
    (net (code "63") (name "Net-(E14C-I0)") (class "Default")
      (node (ref "E14") (pin "8") (pinfunction "I0_8") (pintype "input"))
      (node (ref "E17") (pin "3") (pinfunction "O_3") (pintype "output"))
    )
    (net (code "64") (name "Net-(E14D-I0)") (class "Default")
      (node (ref "E14") (pin "11") (pinfunction "I0_11") (pintype "input"))
      (node (ref "E17") (pin "2") (pinfunction "O_2") (pintype "output"))
    )
    (net (code "65") (name "Net-(E17A-I0)") (class "Default")
      (node (ref "D101") (pin "A") (pinfunction "A_A") (pintype "passive"))
      (node (ref "D113") (pin "A") (pinfunction "A_A") (pintype "passive"))
      (node (ref "D125") (pin "A") (pinfunction "A_A") (pintype "passive"))
      (node (ref "D137") (pin "A") (pinfunction "A_A") (pintype "passive"))
      (node (ref "D149") (pin "A") (pinfunction "A_A") (pintype "passive"))
      (node (ref "D161") (pin "A") (pinfunction "A_A") (pintype "passive"))
      (node (ref "D17") (pin "A") (pinfunction "A_A") (pintype "passive"))
      (node (ref "D173") (pin "A") (pinfunction "A_A") (pintype "passive"))
      (node (ref "D185") (pin "A") (pinfunction "A_A") (pintype "passive"))
      (node (ref "D197") (pin "A") (pinfunction "A_A") (pintype "passive"))
      (node (ref "D209") (pin "A") (pinfunction "A_A") (pintype "passive"))
      (node (ref "D221") (pin "A") (pinfunction "A_A") (pintype "passive"))
      (node (ref "D233") (pin "A") (pinfunction "A_A") (pintype "passive"))
      (node (ref "D245") (pin "A") (pinfunction "A_A") (pintype "passive"))
      (node (ref "D257") (pin "A") (pinfunction "A_A") (pintype "passive"))
      (node (ref "D269") (pin "A") (pinfunction "A_A") (pintype "passive"))
      (node (ref "D281") (pin "A") (pinfunction "A_A") (pintype "passive"))
      (node (ref "D29") (pin "A") (pinfunction "A_A") (pintype "passive"))
      (node (ref "D293") (pin "A") (pinfunction "A_A") (pintype "passive"))
      (node (ref "D305") (pin "A") (pinfunction "A_A") (pintype "passive"))
      (node (ref "D317") (pin "A") (pinfunction "A_A") (pintype "passive"))
      (node (ref "D329") (pin "A") (pinfunction "A_A") (pintype "passive"))
      (node (ref "D341") (pin "A") (pinfunction "A_A") (pintype "passive"))
      (node (ref "D353") (pin "A") (pinfunction "A_A") (pintype "passive"))
      (node (ref "D365") (pin "A") (pinfunction "A_A") (pintype "passive"))
      (node (ref "D377") (pin "A") (pinfunction "A_A") (pintype "passive"))
      (node (ref "D41") (pin "A") (pinfunction "A_A") (pintype "passive"))
      (node (ref "D5") (pin "A") (pinfunction "A_A") (pintype "passive"))
      (node (ref "D53") (pin "A") (pinfunction "A_A") (pintype "passive"))
      (node (ref "D65") (pin "A") (pinfunction "A_A") (pintype "passive"))
      (node (ref "D77") (pin "A") (pinfunction "A_A") (pintype "passive"))
      (node (ref "D89") (pin "A") (pinfunction "A_A") (pintype "passive"))
      (node (ref "E17") (pin "4") (pinfunction "I0_4") (pintype "input"))
      (node (ref "E17") (pin "5") (pinfunction "I1_5") (pintype "input"))
    )
    (net (code "66") (name "Net-(E17B-I0)") (class "Default")
      (node (ref "D102") (pin "A") (pinfunction "A_A") (pintype "passive"))
      (node (ref "D114") (pin "A") (pinfunction "A_A") (pintype "passive"))
      (node (ref "D126") (pin "A") (pinfunction "A_A") (pintype "passive"))
      (node (ref "D138") (pin "A") (pinfunction "A_A") (pintype "passive"))
      (node (ref "D150") (pin "A") (pinfunction "A_A") (pintype "passive"))
      (node (ref "D162") (pin "A") (pinfunction "A_A") (pintype "passive"))
      (node (ref "D174") (pin "A") (pinfunction "A_A") (pintype "passive"))
      (node (ref "D18") (pin "A") (pinfunction "A_A") (pintype "passive"))
      (node (ref "D186") (pin "A") (pinfunction "A_A") (pintype "passive"))
      (node (ref "D198") (pin "A") (pinfunction "A_A") (pintype "passive"))
      (node (ref "D210") (pin "A") (pinfunction "A_A") (pintype "passive"))
      (node (ref "D222") (pin "A") (pinfunction "A_A") (pintype "passive"))
      (node (ref "D234") (pin "A") (pinfunction "A_A") (pintype "passive"))
      (node (ref "D246") (pin "A") (pinfunction "A_A") (pintype "passive"))
      (node (ref "D258") (pin "A") (pinfunction "A_A") (pintype "passive"))
      (node (ref "D270") (pin "A") (pinfunction "A_A") (pintype "passive"))
      (node (ref "D282") (pin "A") (pinfunction "A_A") (pintype "passive"))
      (node (ref "D294") (pin "A") (pinfunction "A_A") (pintype "passive"))
      (node (ref "D30") (pin "A") (pinfunction "A_A") (pintype "passive"))
      (node (ref "D306") (pin "A") (pinfunction "A_A") (pintype "passive"))
      (node (ref "D318") (pin "A") (pinfunction "A_A") (pintype "passive"))
      (node (ref "D330") (pin "A") (pinfunction "A_A") (pintype "passive"))
      (node (ref "D342") (pin "A") (pinfunction "A_A") (pintype "passive"))
      (node (ref "D354") (pin "A") (pinfunction "A_A") (pintype "passive"))
      (node (ref "D366") (pin "A") (pinfunction "A_A") (pintype "passive"))
      (node (ref "D378") (pin "A") (pinfunction "A_A") (pintype "passive"))
      (node (ref "D42") (pin "A") (pinfunction "A_A") (pintype "passive"))
      (node (ref "D54") (pin "A") (pinfunction "A_A") (pintype "passive"))
      (node (ref "D6") (pin "A") (pinfunction "A_A") (pintype "passive"))
      (node (ref "D66") (pin "A") (pinfunction "A_A") (pintype "passive"))
      (node (ref "D78") (pin "A") (pinfunction "A_A") (pintype "passive"))
      (node (ref "D90") (pin "A") (pinfunction "A_A") (pintype "passive"))
      (node (ref "E17") (pin "6") (pinfunction "I0_6") (pintype "input"))
      (node (ref "E17") (pin "7") (pinfunction "I1_7") (pintype "input"))
    )
    (net (code "67") (name "Net-(E17C-I0)") (class "Default")
      (node (ref "D104") (pin "A") (pinfunction "A_A") (pintype "passive"))
      (node (ref "D116") (pin "A") (pinfunction "A_A") (pintype "passive"))
      (node (ref "D128") (pin "A") (pinfunction "A_A") (pintype "passive"))
      (node (ref "D140") (pin "A") (pinfunction "A_A") (pintype "passive"))
      (node (ref "D152") (pin "A") (pinfunction "A_A") (pintype "passive"))
      (node (ref "D164") (pin "A") (pinfunction "A_A") (pintype "passive"))
      (node (ref "D176") (pin "A") (pinfunction "A_A") (pintype "passive"))
      (node (ref "D188") (pin "A") (pinfunction "A_A") (pintype "passive"))
      (node (ref "D20") (pin "A") (pinfunction "A_A") (pintype "passive"))
      (node (ref "D200") (pin "A") (pinfunction "A_A") (pintype "passive"))
      (node (ref "D212") (pin "A") (pinfunction "A_A") (pintype "passive"))
      (node (ref "D224") (pin "A") (pinfunction "A_A") (pintype "passive"))
      (node (ref "D236") (pin "A") (pinfunction "A_A") (pintype "passive"))
      (node (ref "D248") (pin "A") (pinfunction "A_A") (pintype "passive"))
      (node (ref "D260") (pin "A") (pinfunction "A_A") (pintype "passive"))
      (node (ref "D272") (pin "A") (pinfunction "A_A") (pintype "passive"))
      (node (ref "D284") (pin "A") (pinfunction "A_A") (pintype "passive"))
      (node (ref "D296") (pin "A") (pinfunction "A_A") (pintype "passive"))
      (node (ref "D308") (pin "A") (pinfunction "A_A") (pintype "passive"))
      (node (ref "D32") (pin "A") (pinfunction "A_A") (pintype "passive"))
      (node (ref "D320") (pin "A") (pinfunction "A_A") (pintype "passive"))
      (node (ref "D332") (pin "A") (pinfunction "A_A") (pintype "passive"))
      (node (ref "D344") (pin "A") (pinfunction "A_A") (pintype "passive"))
      (node (ref "D356") (pin "A") (pinfunction "A_A") (pintype "passive"))
      (node (ref "D368") (pin "A") (pinfunction "A_A") (pintype "passive"))
      (node (ref "D380") (pin "A") (pinfunction "A_A") (pintype "passive"))
      (node (ref "D44") (pin "A") (pinfunction "A_A") (pintype "passive"))
      (node (ref "D56") (pin "A") (pinfunction "A_A") (pintype "passive"))
      (node (ref "D68") (pin "A") (pinfunction "A_A") (pintype "passive"))
      (node (ref "D8") (pin "A") (pinfunction "A_A") (pintype "passive"))
      (node (ref "D80") (pin "A") (pinfunction "A_A") (pintype "passive"))
      (node (ref "D92") (pin "A") (pinfunction "A_A") (pintype "passive"))
      (node (ref "E17") (pin "10") (pinfunction "I1_10") (pintype "input"))
      (node (ref "E17") (pin "9") (pinfunction "I0_9") (pintype "input"))
    )
    (net (code "68") (name "Net-(E17D-I0)") (class "Default")
      (node (ref "D103") (pin "A") (pinfunction "A_A") (pintype "passive"))
      (node (ref "D115") (pin "A") (pinfunction "A_A") (pintype "passive"))
      (node (ref "D127") (pin "A") (pinfunction "A_A") (pintype "passive"))
      (node (ref "D139") (pin "A") (pinfunction "A_A") (pintype "passive"))
      (node (ref "D151") (pin "A") (pinfunction "A_A") (pintype "passive"))
      (node (ref "D163") (pin "A") (pinfunction "A_A") (pintype "passive"))
      (node (ref "D175") (pin "A") (pinfunction "A_A") (pintype "passive"))
      (node (ref "D187") (pin "A") (pinfunction "A_A") (pintype "passive"))
      (node (ref "D19") (pin "A") (pinfunction "A_A") (pintype "passive"))
      (node (ref "D199") (pin "A") (pinfunction "A_A") (pintype "passive"))
      (node (ref "D211") (pin "A") (pinfunction "A_A") (pintype "passive"))
      (node (ref "D223") (pin "A") (pinfunction "A_A") (pintype "passive"))
      (node (ref "D235") (pin "A") (pinfunction "A_A") (pintype "passive"))
      (node (ref "D247") (pin "A") (pinfunction "A_A") (pintype "passive"))
      (node (ref "D259") (pin "A") (pinfunction "A_A") (pintype "passive"))
      (node (ref "D271") (pin "A") (pinfunction "A_A") (pintype "passive"))
      (node (ref "D283") (pin "A") (pinfunction "A_A") (pintype "passive"))
      (node (ref "D295") (pin "A") (pinfunction "A_A") (pintype "passive"))
      (node (ref "D307") (pin "A") (pinfunction "A_A") (pintype "passive"))
      (node (ref "D31") (pin "A") (pinfunction "A_A") (pintype "passive"))
      (node (ref "D319") (pin "A") (pinfunction "A_A") (pintype "passive"))
      (node (ref "D331") (pin "A") (pinfunction "A_A") (pintype "passive"))
      (node (ref "D343") (pin "A") (pinfunction "A_A") (pintype "passive"))
      (node (ref "D355") (pin "A") (pinfunction "A_A") (pintype "passive"))
      (node (ref "D367") (pin "A") (pinfunction "A_A") (pintype "passive"))
      (node (ref "D379") (pin "A") (pinfunction "A_A") (pintype "passive"))
      (node (ref "D43") (pin "A") (pinfunction "A_A") (pintype "passive"))
      (node (ref "D55") (pin "A") (pinfunction "A_A") (pintype "passive"))
      (node (ref "D67") (pin "A") (pinfunction "A_A") (pintype "passive"))
      (node (ref "D7") (pin "A") (pinfunction "A_A") (pintype "passive"))
      (node (ref "D79") (pin "A") (pinfunction "A_A") (pintype "passive"))
      (node (ref "D91") (pin "A") (pinfunction "A_A") (pintype "passive"))
      (node (ref "E17") (pin "11") (pinfunction "I0_11") (pintype "input"))
      (node (ref "E17") (pin "12") (pinfunction "I1_12") (pintype "input"))
    )
    (net (code "69") (name "Net-(E24A-I)") (class "Default")
      (node (ref "E24") (pin "1") (pinfunction "I_1") (pintype "input"))
      (node (ref "E25") (pin "10") (pinfunction "QE_10") (pintype "output"))
    )
    (net (code "70") (name "Net-(E24D-I)") (class "Default")
      (node (ref "E24") (pin "9") (pinfunction "I_9") (pintype "input"))
      (node (ref "E25") (pin "13") (pinfunction "QH_13") (pintype "output"))
      (node (ref "E9") (pin "1") (pinfunction "A_1") (pintype "input"))
      (node (ref "E9") (pin "2") (pinfunction "B_2") (pintype "input"))
    )
    (net (code "71") (name "Net-(E24E-I)") (class "Default")
      (node (ref "E24") (pin "11") (pinfunction "I_11") (pintype "input"))
      (node (ref "E25") (pin "12") (pinfunction "QG_12") (pintype "output"))
    )
    (net (code "72") (name "Net-(E24F-I)") (class "Default")
      (node (ref "E24") (pin "13") (pinfunction "I_13") (pintype "input"))
      (node (ref "E25") (pin "11") (pinfunction "QF_11") (pintype "output"))
    )
    (net (code "73") (name "Net-(E25A-A)") (class "Default")
      (node (ref "E25") (pin "1") (pinfunction "A_1") (pintype "input"))
      (node (ref "E25") (pin "2") (pinfunction "B_2") (pintype "input"))
      (node (ref "E28") (pin "3") (pinfunction "I_3") (pintype "input"))
      (node (ref "E31") (pin "13") (pinfunction "QH_13") (pintype "output"))
    )
    (net (code "74") (name "Net-(E25A-QA)") (class "Default")
      (node (ref "E25") (pin "3") (pinfunction "QA_3") (pintype "output"))
      (node (ref "E28") (pin "1") (pinfunction "I_1") (pintype "input"))
    )
    (net (code "75") (name "Net-(E25A-QB)") (class "Default")
      (node (ref "E25") (pin "4") (pinfunction "QB_4") (pintype "output"))
      (node (ref "E28") (pin "13") (pinfunction "I_13") (pintype "input"))
    )
    (net (code "76") (name "Net-(E25A-QC)") (class "Default")
      (node (ref "E25") (pin "5") (pinfunction "QC_5") (pintype "output"))
      (node (ref "E28") (pin "11") (pinfunction "I_11") (pintype "input"))
    )
    (net (code "77") (name "Net-(E25A-QD)") (class "Default")
      (node (ref "E25") (pin "6") (pinfunction "QD_6") (pintype "output"))
      (node (ref "E28") (pin "9") (pinfunction "I_9") (pintype "input"))
    )
    (net (code "78") (name "Net-(E27A-O)") (class "Default")
      (node (ref "E27") (pin "3") (pinfunction "O_3") (pintype "output"))
      (node (ref "E31") (pin "1") (pinfunction "A_1") (pintype "input"))
      (node (ref "E31") (pin "2") (pinfunction "B_2") (pintype "input"))
    )
    (net (code "79") (name "Net-(E28C-I)") (class "Default")
      (node (ref "E28") (pin "5") (pinfunction "I_5") (pintype "input"))
      (node (ref "E31") (pin "12") (pinfunction "QG_12") (pintype "output"))
    )
    (net (code "80") (name "Net-(E31A-QA)") (class "Default")
      (node (ref "E31") (pin "3") (pinfunction "QA_3") (pintype "output"))
      (node (ref "E34") (pin "5") (pinfunction "I_5") (pintype "input"))
    )
    (net (code "81") (name "Net-(E31A-QB)") (class "Default")
      (node (ref "E31") (pin "4") (pinfunction "QB_4") (pintype "output"))
      (node (ref "E34") (pin "3") (pinfunction "I_3") (pintype "input"))
    )
    (net (code "82") (name "Net-(E31A-QC)") (class "Default")
      (node (ref "E31") (pin "5") (pinfunction "QC_5") (pintype "output"))
      (node (ref "E34") (pin "1") (pinfunction "I_1") (pintype "input"))
    )
    (net (code "83") (name "Net-(E31A-QD)") (class "Default")
      (node (ref "E31") (pin "6") (pinfunction "QD_6") (pintype "output"))
      (node (ref "E34") (pin "13") (pinfunction "I_13") (pintype "input"))
    )
    (net (code "84") (name "Net-(E31A-QE)") (class "Default")
      (node (ref "E31") (pin "10") (pinfunction "QE_10") (pintype "output"))
      (node (ref "E34") (pin "11") (pinfunction "I_11") (pintype "input"))
    )
    (net (code "85") (name "Net-(E31A-QF)") (class "Default")
      (node (ref "E31") (pin "11") (pinfunction "QF_11") (pintype "output"))
      (node (ref "E34") (pin "9") (pinfunction "I_9") (pintype "input"))
    )
    (net (code "86") (name "Net-(E43A-I0)") (class "Default")
      (node (ref "D105") (pin "A") (pinfunction "A_A") (pintype "passive"))
      (node (ref "D117") (pin "A") (pinfunction "A_A") (pintype "passive"))
      (node (ref "D129") (pin "A") (pinfunction "A_A") (pintype "passive"))
      (node (ref "D141") (pin "A") (pinfunction "A_A") (pintype "passive"))
      (node (ref "D153") (pin "A") (pinfunction "A_A") (pintype "passive"))
      (node (ref "D165") (pin "A") (pinfunction "A_A") (pintype "passive"))
      (node (ref "D177") (pin "A") (pinfunction "A_A") (pintype "passive"))
      (node (ref "D189") (pin "A") (pinfunction "A_A") (pintype "passive"))
      (node (ref "D201") (pin "A") (pinfunction "A_A") (pintype "passive"))
      (node (ref "D21") (pin "A") (pinfunction "A_A") (pintype "passive"))
      (node (ref "D213") (pin "A") (pinfunction "A_A") (pintype "passive"))
      (node (ref "D225") (pin "A") (pinfunction "A_A") (pintype "passive"))
      (node (ref "D237") (pin "A") (pinfunction "A_A") (pintype "passive"))
      (node (ref "D249") (pin "A") (pinfunction "A_A") (pintype "passive"))
      (node (ref "D261") (pin "A") (pinfunction "A_A") (pintype "passive"))
      (node (ref "D273") (pin "A") (pinfunction "A_A") (pintype "passive"))
      (node (ref "D285") (pin "A") (pinfunction "A_A") (pintype "passive"))
      (node (ref "D297") (pin "A") (pinfunction "A_A") (pintype "passive"))
      (node (ref "D309") (pin "A") (pinfunction "A_A") (pintype "passive"))
      (node (ref "D321") (pin "A") (pinfunction "A_A") (pintype "passive"))
      (node (ref "D33") (pin "A") (pinfunction "A_A") (pintype "passive"))
      (node (ref "D333") (pin "A") (pinfunction "A_A") (pintype "passive"))
      (node (ref "D345") (pin "A") (pinfunction "A_A") (pintype "passive"))
      (node (ref "D357") (pin "A") (pinfunction "A_A") (pintype "passive"))
      (node (ref "D369") (pin "A") (pinfunction "A_A") (pintype "passive"))
      (node (ref "D381") (pin "A") (pinfunction "A_A") (pintype "passive"))
      (node (ref "D45") (pin "A") (pinfunction "A_A") (pintype "passive"))
      (node (ref "D57") (pin "A") (pinfunction "A_A") (pintype "passive"))
      (node (ref "D69") (pin "A") (pinfunction "A_A") (pintype "passive"))
      (node (ref "D81") (pin "A") (pinfunction "A_A") (pintype "passive"))
      (node (ref "D9") (pin "A") (pinfunction "A_A") (pintype "passive"))
      (node (ref "D93") (pin "A") (pinfunction "A_A") (pintype "passive"))
      (node (ref "E43") (pin "4") (pinfunction "I0_4") (pintype "input"))
      (node (ref "E43") (pin "5") (pinfunction "I1_5") (pintype "input"))
    )
    (net (code "87") (name "Net-(E43A-O)") (class "Default")
      (node (ref "E43") (pin "3") (pinfunction "O_3") (pintype "output"))
      (node (ref "IC7") (pin "8") (pinfunction "I0_8") (pintype "input"))
    )
    (net (code "88") (name "Net-(E43B-I0)") (class "Default")
      (node (ref "D10") (pin "A") (pinfunction "A_A") (pintype "passive"))
      (node (ref "D106") (pin "A") (pinfunction "A_A") (pintype "passive"))
      (node (ref "D118") (pin "A") (pinfunction "A_A") (pintype "passive"))
      (node (ref "D130") (pin "A") (pinfunction "A_A") (pintype "passive"))
      (node (ref "D142") (pin "A") (pinfunction "A_A") (pintype "passive"))
      (node (ref "D154") (pin "A") (pinfunction "A_A") (pintype "passive"))
      (node (ref "D166") (pin "A") (pinfunction "A_A") (pintype "passive"))
      (node (ref "D178") (pin "A") (pinfunction "A_A") (pintype "passive"))
      (node (ref "D190") (pin "A") (pinfunction "A_A") (pintype "passive"))
      (node (ref "D202") (pin "A") (pinfunction "A_A") (pintype "passive"))
      (node (ref "D214") (pin "A") (pinfunction "A_A") (pintype "passive"))
      (node (ref "D22") (pin "A") (pinfunction "A_A") (pintype "passive"))
      (node (ref "D226") (pin "A") (pinfunction "A_A") (pintype "passive"))
      (node (ref "D238") (pin "A") (pinfunction "A_A") (pintype "passive"))
      (node (ref "D250") (pin "A") (pinfunction "A_A") (pintype "passive"))
      (node (ref "D262") (pin "A") (pinfunction "A_A") (pintype "passive"))
      (node (ref "D274") (pin "A") (pinfunction "A_A") (pintype "passive"))
      (node (ref "D286") (pin "A") (pinfunction "A_A") (pintype "passive"))
      (node (ref "D298") (pin "A") (pinfunction "A_A") (pintype "passive"))
      (node (ref "D310") (pin "A") (pinfunction "A_A") (pintype "passive"))
      (node (ref "D322") (pin "A") (pinfunction "A_A") (pintype "passive"))
      (node (ref "D334") (pin "A") (pinfunction "A_A") (pintype "passive"))
      (node (ref "D34") (pin "A") (pinfunction "A_A") (pintype "passive"))
      (node (ref "D346") (pin "A") (pinfunction "A_A") (pintype "passive"))
      (node (ref "D358") (pin "A") (pinfunction "A_A") (pintype "passive"))
      (node (ref "D370") (pin "A") (pinfunction "A_A") (pintype "passive"))
      (node (ref "D382") (pin "A") (pinfunction "A_A") (pintype "passive"))
      (node (ref "D46") (pin "A") (pinfunction "A_A") (pintype "passive"))
      (node (ref "D58") (pin "A") (pinfunction "A_A") (pintype "passive"))
      (node (ref "D70") (pin "A") (pinfunction "A_A") (pintype "passive"))
      (node (ref "D82") (pin "A") (pinfunction "A_A") (pintype "passive"))
      (node (ref "D94") (pin "A") (pinfunction "A_A") (pintype "passive"))
      (node (ref "E43") (pin "6") (pinfunction "I0_6") (pintype "input"))
      (node (ref "E43") (pin "7") (pinfunction "I1_7") (pintype "input"))
    )
    (net (code "89") (name "Net-(E43B-O)") (class "Default")
      (node (ref "E43") (pin "2") (pinfunction "O_2") (pintype "output"))
      (node (ref "IC7") (pin "11") (pinfunction "I0_11") (pintype "input"))
    )
    (net (code "90") (name "Net-(E43C-I0)") (class "Default")
      (node (ref "D108") (pin "A") (pinfunction "A_A") (pintype "passive"))
      (node (ref "D12") (pin "A") (pinfunction "A_A") (pintype "passive"))
      (node (ref "D120") (pin "A") (pinfunction "A_A") (pintype "passive"))
      (node (ref "D132") (pin "A") (pinfunction "A_A") (pintype "passive"))
      (node (ref "D144") (pin "A") (pinfunction "A_A") (pintype "passive"))
      (node (ref "D156") (pin "A") (pinfunction "A_A") (pintype "passive"))
      (node (ref "D168") (pin "A") (pinfunction "A_A") (pintype "passive"))
      (node (ref "D180") (pin "A") (pinfunction "A_A") (pintype "passive"))
      (node (ref "D192") (pin "A") (pinfunction "A_A") (pintype "passive"))
      (node (ref "D204") (pin "A") (pinfunction "A_A") (pintype "passive"))
      (node (ref "D216") (pin "A") (pinfunction "A_A") (pintype "passive"))
      (node (ref "D228") (pin "A") (pinfunction "A_A") (pintype "passive"))
      (node (ref "D24") (pin "A") (pinfunction "A_A") (pintype "passive"))
      (node (ref "D240") (pin "A") (pinfunction "A_A") (pintype "passive"))
      (node (ref "D252") (pin "A") (pinfunction "A_A") (pintype "passive"))
      (node (ref "D264") (pin "A") (pinfunction "A_A") (pintype "passive"))
      (node (ref "D276") (pin "A") (pinfunction "A_A") (pintype "passive"))
      (node (ref "D288") (pin "A") (pinfunction "A_A") (pintype "passive"))
      (node (ref "D300") (pin "A") (pinfunction "A_A") (pintype "passive"))
      (node (ref "D312") (pin "A") (pinfunction "A_A") (pintype "passive"))
      (node (ref "D324") (pin "A") (pinfunction "A_A") (pintype "passive"))
      (node (ref "D336") (pin "A") (pinfunction "A_A") (pintype "passive"))
      (node (ref "D348") (pin "A") (pinfunction "A_A") (pintype "passive"))
      (node (ref "D36") (pin "A") (pinfunction "A_A") (pintype "passive"))
      (node (ref "D360") (pin "A") (pinfunction "A_A") (pintype "passive"))
      (node (ref "D372") (pin "A") (pinfunction "A_A") (pintype "passive"))
      (node (ref "D384") (pin "A") (pinfunction "A_A") (pintype "passive"))
      (node (ref "D48") (pin "A") (pinfunction "A_A") (pintype "passive"))
      (node (ref "D60") (pin "A") (pinfunction "A_A") (pintype "passive"))
      (node (ref "D72") (pin "A") (pinfunction "A_A") (pintype "passive"))
      (node (ref "D84") (pin "A") (pinfunction "A_A") (pintype "passive"))
      (node (ref "D96") (pin "A") (pinfunction "A_A") (pintype "passive"))
      (node (ref "E43") (pin "10") (pinfunction "I1_10") (pintype "input"))
      (node (ref "E43") (pin "9") (pinfunction "I0_9") (pintype "input"))
    )
    (net (code "91") (name "Net-(E43C-O)") (class "Default")
      (node (ref "E43") (pin "14") (pinfunction "O_14") (pintype "output"))
      (node (ref "IC7") (pin "2") (pinfunction "I0_2") (pintype "input"))
    )
    (net (code "92") (name "Net-(E43D-I0)") (class "Default")
      (node (ref "D107") (pin "A") (pinfunction "A_A") (pintype "passive"))
      (node (ref "D11") (pin "A") (pinfunction "A_A") (pintype "passive"))
      (node (ref "D119") (pin "A") (pinfunction "A_A") (pintype "passive"))
      (node (ref "D131") (pin "A") (pinfunction "A_A") (pintype "passive"))
      (node (ref "D143") (pin "A") (pinfunction "A_A") (pintype "passive"))
      (node (ref "D155") (pin "A") (pinfunction "A_A") (pintype "passive"))
      (node (ref "D167") (pin "A") (pinfunction "A_A") (pintype "passive"))
      (node (ref "D179") (pin "A") (pinfunction "A_A") (pintype "passive"))
      (node (ref "D191") (pin "A") (pinfunction "A_A") (pintype "passive"))
      (node (ref "D203") (pin "A") (pinfunction "A_A") (pintype "passive"))
      (node (ref "D215") (pin "A") (pinfunction "A_A") (pintype "passive"))
      (node (ref "D227") (pin "A") (pinfunction "A_A") (pintype "passive"))
      (node (ref "D23") (pin "A") (pinfunction "A_A") (pintype "passive"))
      (node (ref "D239") (pin "A") (pinfunction "A_A") (pintype "passive"))
      (node (ref "D251") (pin "A") (pinfunction "A_A") (pintype "passive"))
      (node (ref "D263") (pin "A") (pinfunction "A_A") (pintype "passive"))
      (node (ref "D275") (pin "A") (pinfunction "A_A") (pintype "passive"))
      (node (ref "D287") (pin "A") (pinfunction "A_A") (pintype "passive"))
      (node (ref "D299") (pin "A") (pinfunction "A_A") (pintype "passive"))
      (node (ref "D311") (pin "A") (pinfunction "A_A") (pintype "passive"))
      (node (ref "D323") (pin "A") (pinfunction "A_A") (pintype "passive"))
      (node (ref "D335") (pin "A") (pinfunction "A_A") (pintype "passive"))
      (node (ref "D347") (pin "A") (pinfunction "A_A") (pintype "passive"))
      (node (ref "D35") (pin "A") (pinfunction "A_A") (pintype "passive"))
      (node (ref "D359") (pin "A") (pinfunction "A_A") (pintype "passive"))
      (node (ref "D371") (pin "A") (pinfunction "A_A") (pintype "passive"))
      (node (ref "D383") (pin "A") (pinfunction "A_A") (pintype "passive"))
      (node (ref "D47") (pin "A") (pinfunction "A_A") (pintype "passive"))
      (node (ref "D59") (pin "A") (pinfunction "A_A") (pintype "passive"))
      (node (ref "D71") (pin "A") (pinfunction "A_A") (pintype "passive"))
      (node (ref "D83") (pin "A") (pinfunction "A_A") (pintype "passive"))
      (node (ref "D95") (pin "A") (pinfunction "A_A") (pintype "passive"))
      (node (ref "E43") (pin "11") (pinfunction "I0_11") (pintype "input"))
      (node (ref "E43") (pin "12") (pinfunction "I1_12") (pintype "input"))
    )
    (net (code "93") (name "Net-(E43D-O)") (class "Default")
      (node (ref "E43") (pin "13") (pinfunction "O_13") (pintype "output"))
      (node (ref "IC7") (pin "5") (pinfunction "I0_5") (pintype "input"))
    )
    (net (code "94") (name "POWER_OK") (class "Default")
      (node (ref "U$2") (pin "BV2") (pinfunction "1_BV2") (pintype "bidirectional"))
    )
    (net (code "95") (name "PULSE_LA") (class "Default")
      (node (ref "U$2") (pin "DR2") (pinfunction "1_DR2") (pintype "bidirectional"))
    )
    (net (code "96") (name "SW") (class "Default")
      (node (ref "U$2") (pin "DV2") (pinfunction "1_DV2") (pintype "bidirectional"))
    )
    (net (code "97") (name "SYSTEM_CLOCK") (class "Default")
      (node (ref "E25") (pin "8") (pinfunction "CLK_8") (pintype "input"))
      (node (ref "E31") (pin "8") (pinfunction "CLK_8") (pintype "input"))
      (node (ref "E6") (pin "8") (pinfunction "CLK_8") (pintype "input"))
      (node (ref "E9") (pin "8") (pinfunction "CLK_8") (pintype "input"))
    )
    (net (code "98") (name "TP4") (class "Default")
      (node (ref "U$2") (pin "CJ2") (pinfunction "1_CJ2") (pintype "bidirectional"))
    )
    (net (code "99") (name "TP_AB1") (class "Default")
      (node (ref "U$2") (pin "AB1") (pinfunction "1_AB1") (pintype "bidirectional"))
    )
    (net (code "100") (name "TP_CB1") (class "Default")
      (node (ref "U$2") (pin "CB1") (pinfunction "1_CB1") (pintype "bidirectional"))
    )
    (net (code "101") (name "TP_DA1") (class "Default")
      (node (ref "U$2") (pin "DA1") (pinfunction "1_DA1") (pintype "bidirectional"))
    )
    (net (code "102") (name "VCC") (class "Default")
      (node (ref "U$2") (pin "AA2") (pinfunction "1_AA2") (pintype "bidirectional"))
      (node (ref "U$2") (pin "BA2") (pinfunction "1_BA2") (pintype "bidirectional"))
      (node (ref "U$2") (pin "CA2") (pinfunction "1_CA2") (pintype "bidirectional"))
    )
    (net (code "103") (name "unconnected-(E27B-O-Pad2)") (class "Default")
      (node (ref "E27") (pin "2") (pinfunction "O_2") (pintype "output"))
    )
    (net (code "104") (name "~{DATA00}") (class "Default")
      (node (ref "E4") (pin "10") (pinfunction "O_10") (pintype "open_collector"))
      (node (ref "U$2") (pin "AR1") (pinfunction "1_AR1") (pintype "bidirectional"))
    )
    (net (code "105") (name "~{DATA01}") (class "Default")
      (node (ref "E4") (pin "13") (pinfunction "O_13") (pintype "open_collector"))
      (node (ref "U$2") (pin "AS1") (pinfunction "1_AS1") (pintype "bidirectional"))
    )
    (net (code "106") (name "~{DATA02}") (class "Default")
      (node (ref "E4") (pin "4") (pinfunction "O_4") (pintype "open_collector"))
      (node (ref "U$2") (pin "AU1") (pinfunction "1_AU1") (pintype "bidirectional"))
    )
    (net (code "107") (name "~{DATA03}") (class "Default")
      (node (ref "E4") (pin "1") (pinfunction "O_1") (pintype "open_collector"))
      (node (ref "U$2") (pin "AV1") (pinfunction "1_AV1") (pintype "bidirectional"))
    )
    (net (code "108") (name "~{DATA04}") (class "Default")
      (node (ref "E14") (pin "10") (pinfunction "O_10") (pintype "open_collector"))
      (node (ref "U$2") (pin "BR1") (pinfunction "1_BR1") (pintype "bidirectional"))
    )
    (net (code "109") (name "~{DATA05}") (class "Default")
      (node (ref "E14") (pin "13") (pinfunction "O_13") (pintype "open_collector"))
      (node (ref "U$2") (pin "BS1") (pinfunction "1_BS1") (pintype "bidirectional"))
    )
    (net (code "110") (name "~{DATA06}") (class "Default")
      (node (ref "E14") (pin "4") (pinfunction "O_4") (pintype "open_collector"))
      (node (ref "U$2") (pin "BU1") (pinfunction "1_BU1") (pintype "bidirectional"))
    )
    (net (code "111") (name "~{DATA07}") (class "Default")
      (node (ref "E14") (pin "1") (pinfunction "O_1") (pintype "open_collector"))
      (node (ref "U$2") (pin "BV1") (pinfunction "1_BV1") (pintype "bidirectional"))
    )
    (net (code "112") (name "~{DATA08}") (class "Default")
      (node (ref "IC7") (pin "10") (pinfunction "O_10") (pintype "open_collector"))
      (node (ref "U$2") (pin "DR1") (pinfunction "1_DR1") (pintype "bidirectional"))
    )
    (net (code "113") (name "~{DATA09}") (class "Default")
      (node (ref "IC7") (pin "13") (pinfunction "O_13") (pintype "open_collector"))
      (node (ref "U$2") (pin "DS1") (pinfunction "1_DS1") (pintype "bidirectional"))
    )
    (net (code "114") (name "~{DATA10}") (class "Default")
      (node (ref "IC7") (pin "4") (pinfunction "O_4") (pintype "open_collector"))
      (node (ref "U$2") (pin "DU1") (pinfunction "1_DU1") (pintype "bidirectional"))
    )
    (net (code "115") (name "~{DATA11}") (class "Default")
      (node (ref "IC7") (pin "1") (pinfunction "O_1") (pintype "open_collector"))
      (node (ref "U$2") (pin "DV1") (pinfunction "1_DV1") (pintype "bidirectional"))
    )
    (net (code "116") (name "~{KEY_CONTROL}") (class "Default")
      (node (ref "U$2") (pin "DU2") (pinfunction "1_DU2") (pintype "bidirectional"))
    )
    (net (code "117") (name "~{LA_ENABLE}") (class "Default")
      (node (ref "U$2") (pin "BM2") (pinfunction "1_BM2") (pintype "bidirectional"))
    )
    (net (code "118") (name "~{MEM_START}") (class "Default")
      (node (ref "U$2") (pin "AJ2") (pinfunction "1_AJ2") (pintype "bidirectional"))
    )
    (net (code "119") (name "~{MSIR_DISABLE}") (class "Default")
      (node (ref "U$2") (pin "CV1") (pinfunction "1_CV1") (pintype "bidirectional"))
    )
    (net (code "120") (name "~{RUN}") (class "Default")
      (node (ref "U$2") (pin "BU2") (pinfunction "1_BU2") (pintype "bidirectional"))
    )
    (net (code "121") (name "~{STOP}") (class "Default")
      (node (ref "U$2") (pin "DS2") (pinfunction "1_DS2") (pintype "bidirectional"))
    )
    (net (code "122") (name "~{SYSTEM_CLEAR}") (class "Default")
      (node (ref "E25") (pin "9") (pinfunction "CLR_9") (pintype "input"))
      (node (ref "E31") (pin "9") (pinfunction "CLR_9") (pintype "input"))
      (node (ref "E6") (pin "9") (pinfunction "CLR_9") (pintype "input"))
      (node (ref "E9") (pin "9") (pinfunction "CLR_9") (pintype "input"))
    )
    (net (code "123") (name "~{TS1}") (class "Default")
      (node (ref "E27") (pin "4") (pinfunction "I0_4") (pintype "input"))
      (node (ref "E27") (pin "5") (pinfunction "I1_5") (pintype "input"))
      (node (ref "U$2") (pin "CK2") (pinfunction "1_CK2") (pintype "bidirectional"))
    )
    (net (code "124") (name "~{TS3}") (class "Default")
      (node (ref "U$2") (pin "CM2") (pinfunction "1_CM2") (pintype "bidirectional"))
    )
  )
)
